# LR1302_LoRaWAN_Gateway_Module_V1_0_915SP.net
KiCad netlist of a schematic drawn in EAGLE
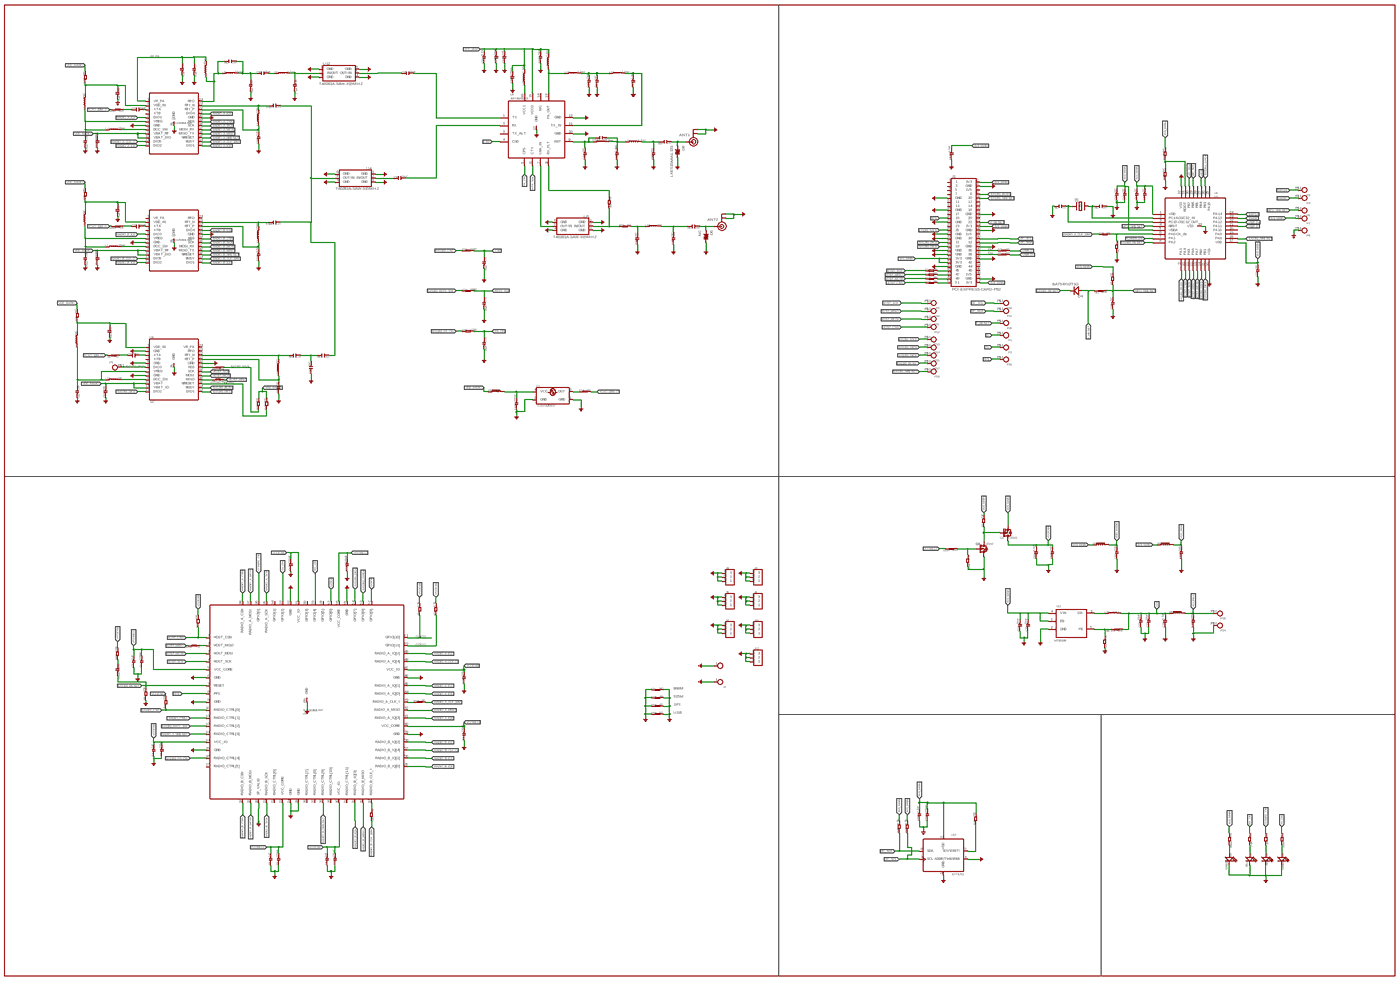
[diagram p0: schematic, sheet 1, overview]
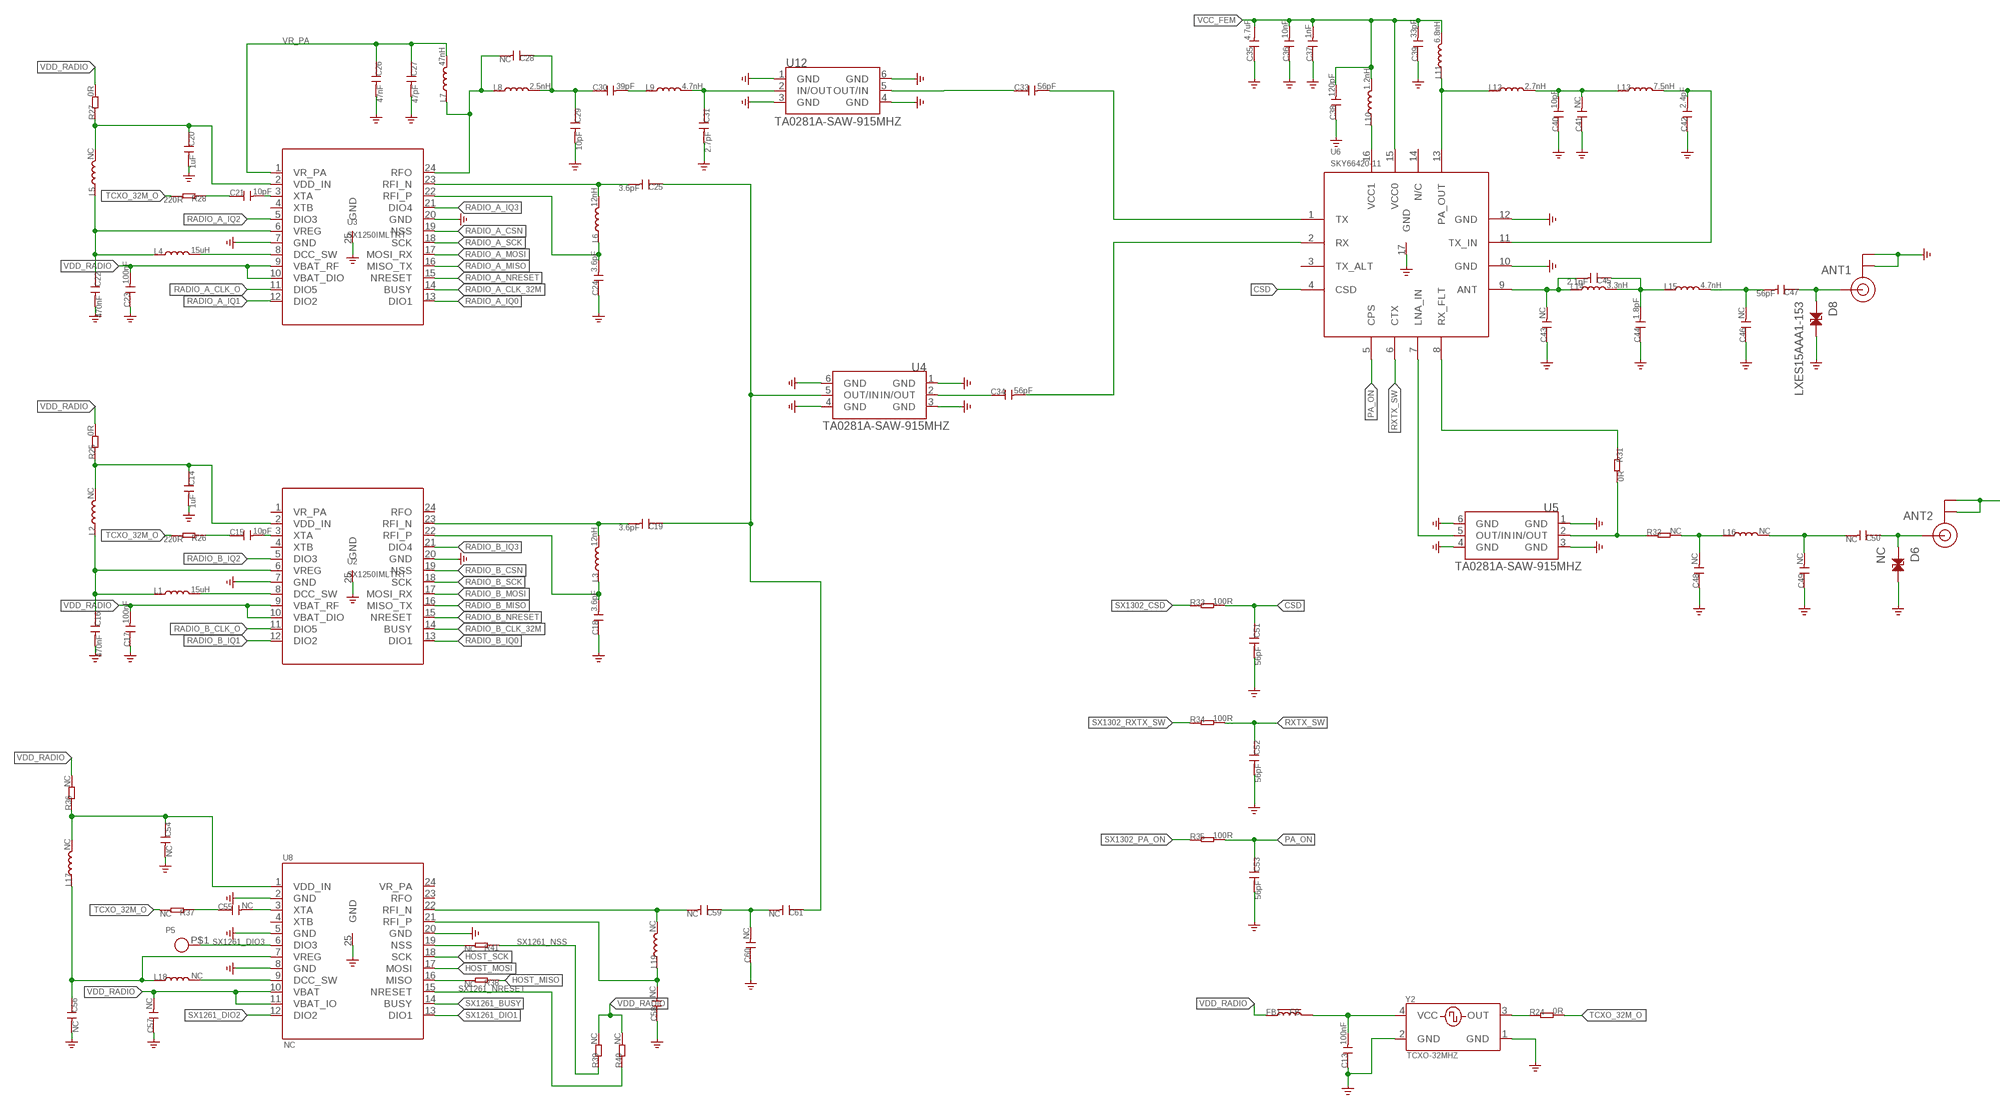
[diagram p1: schematic, sheet 1, part 1 of 4]
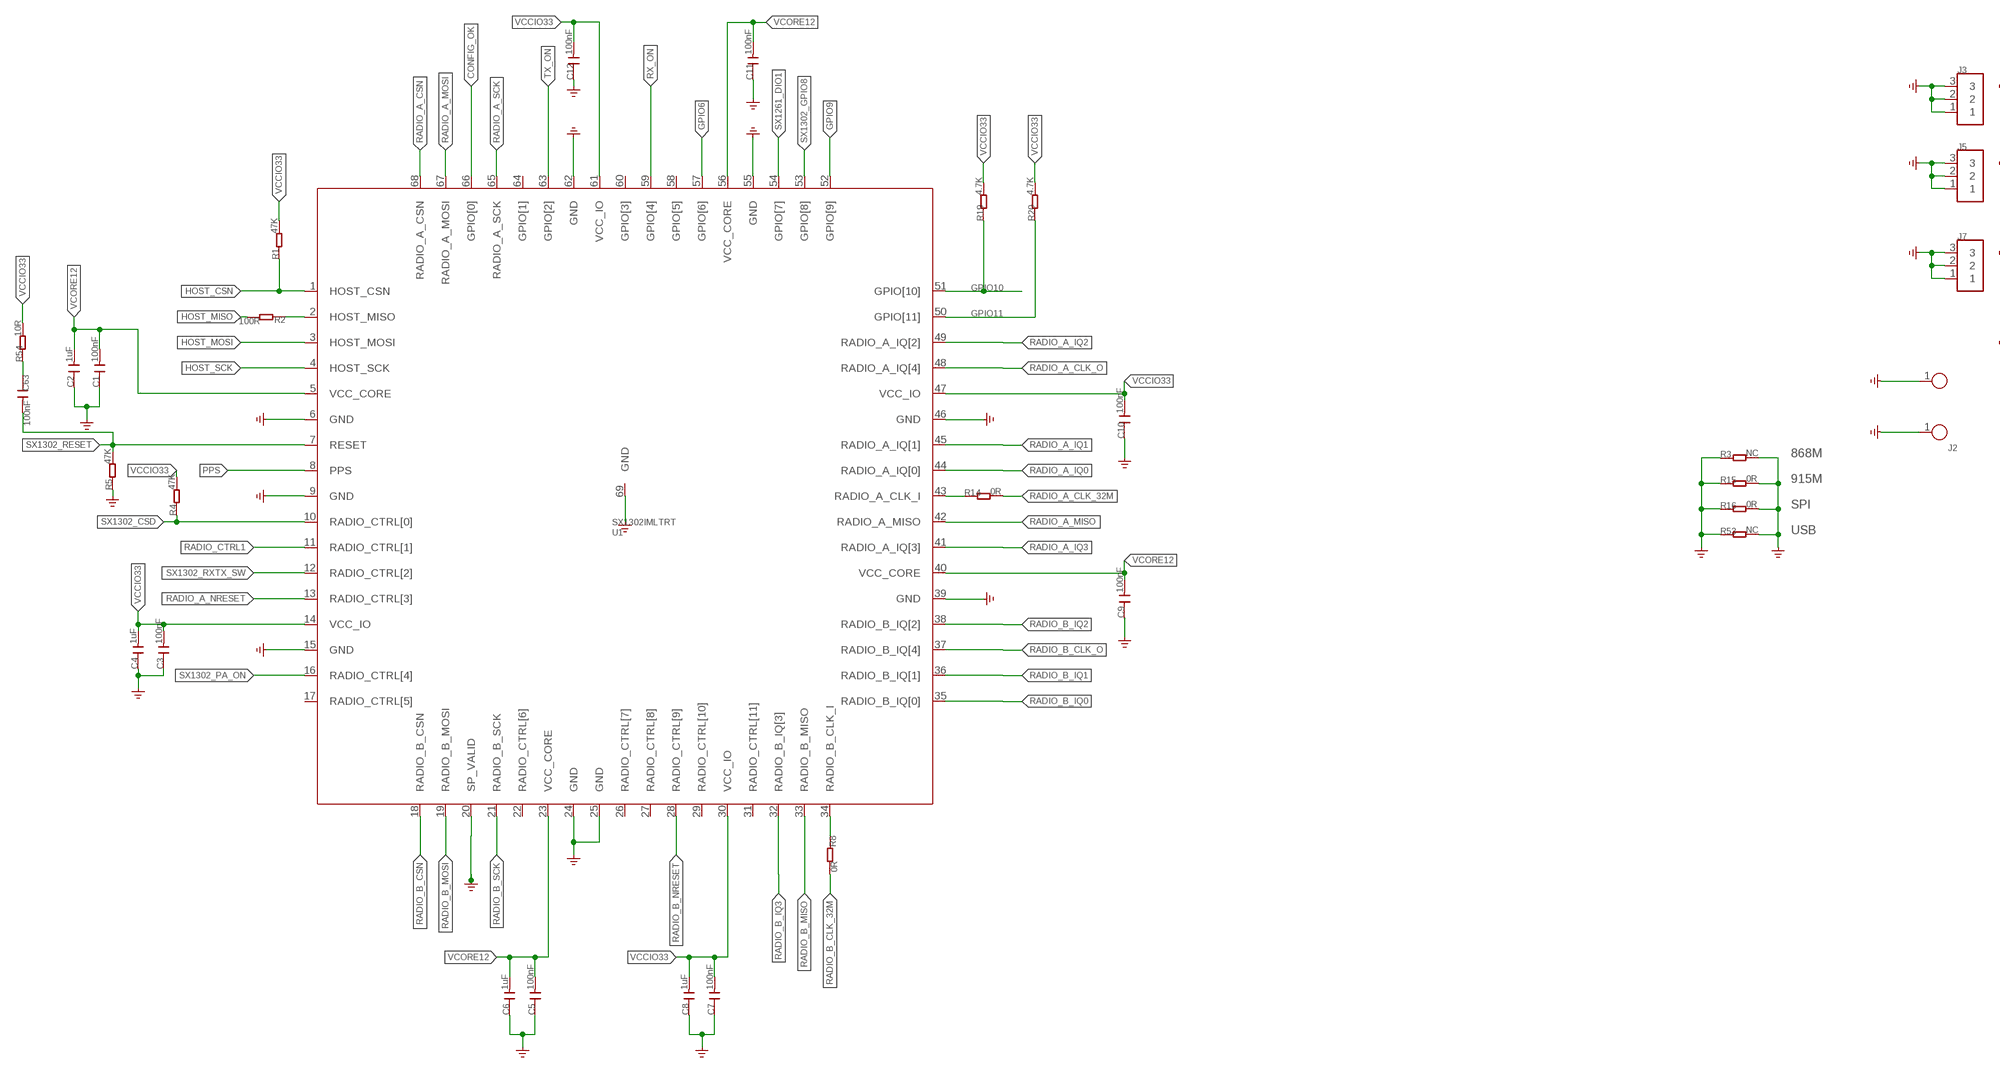
[diagram p2: schematic, sheet 1, part 2 of 4]
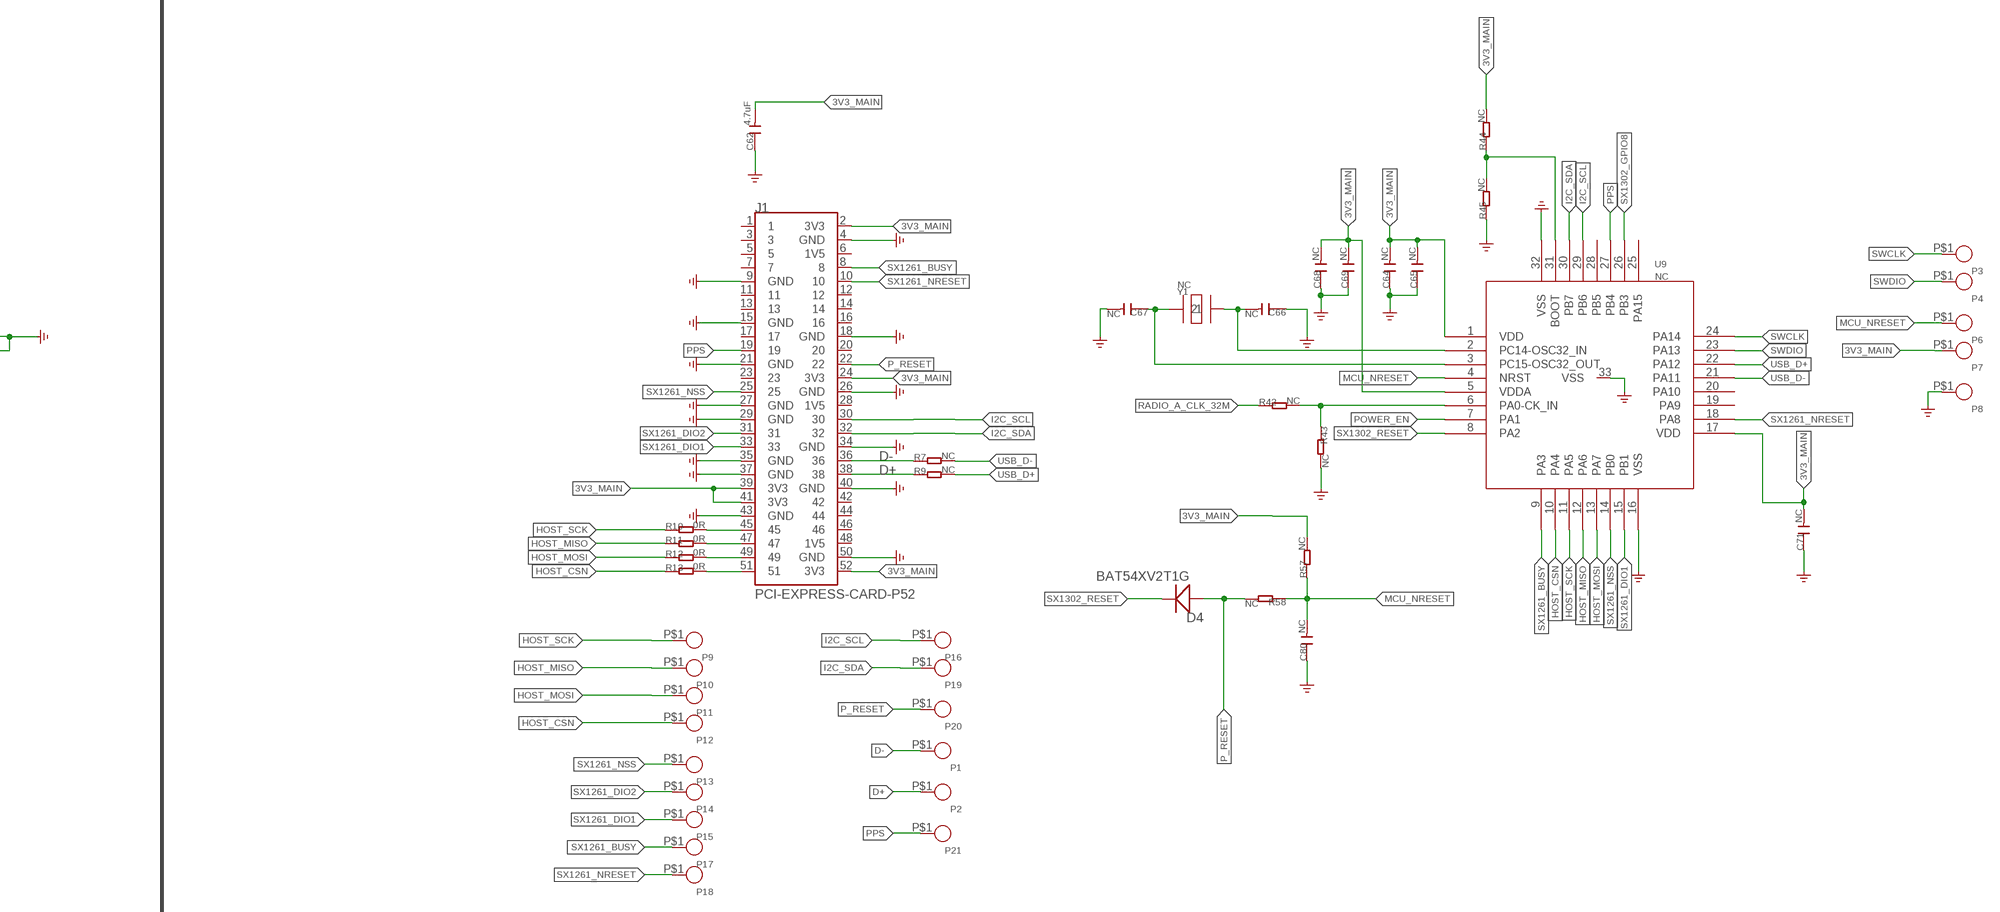
[diagram p3: schematic, sheet 1, part 3 of 4]
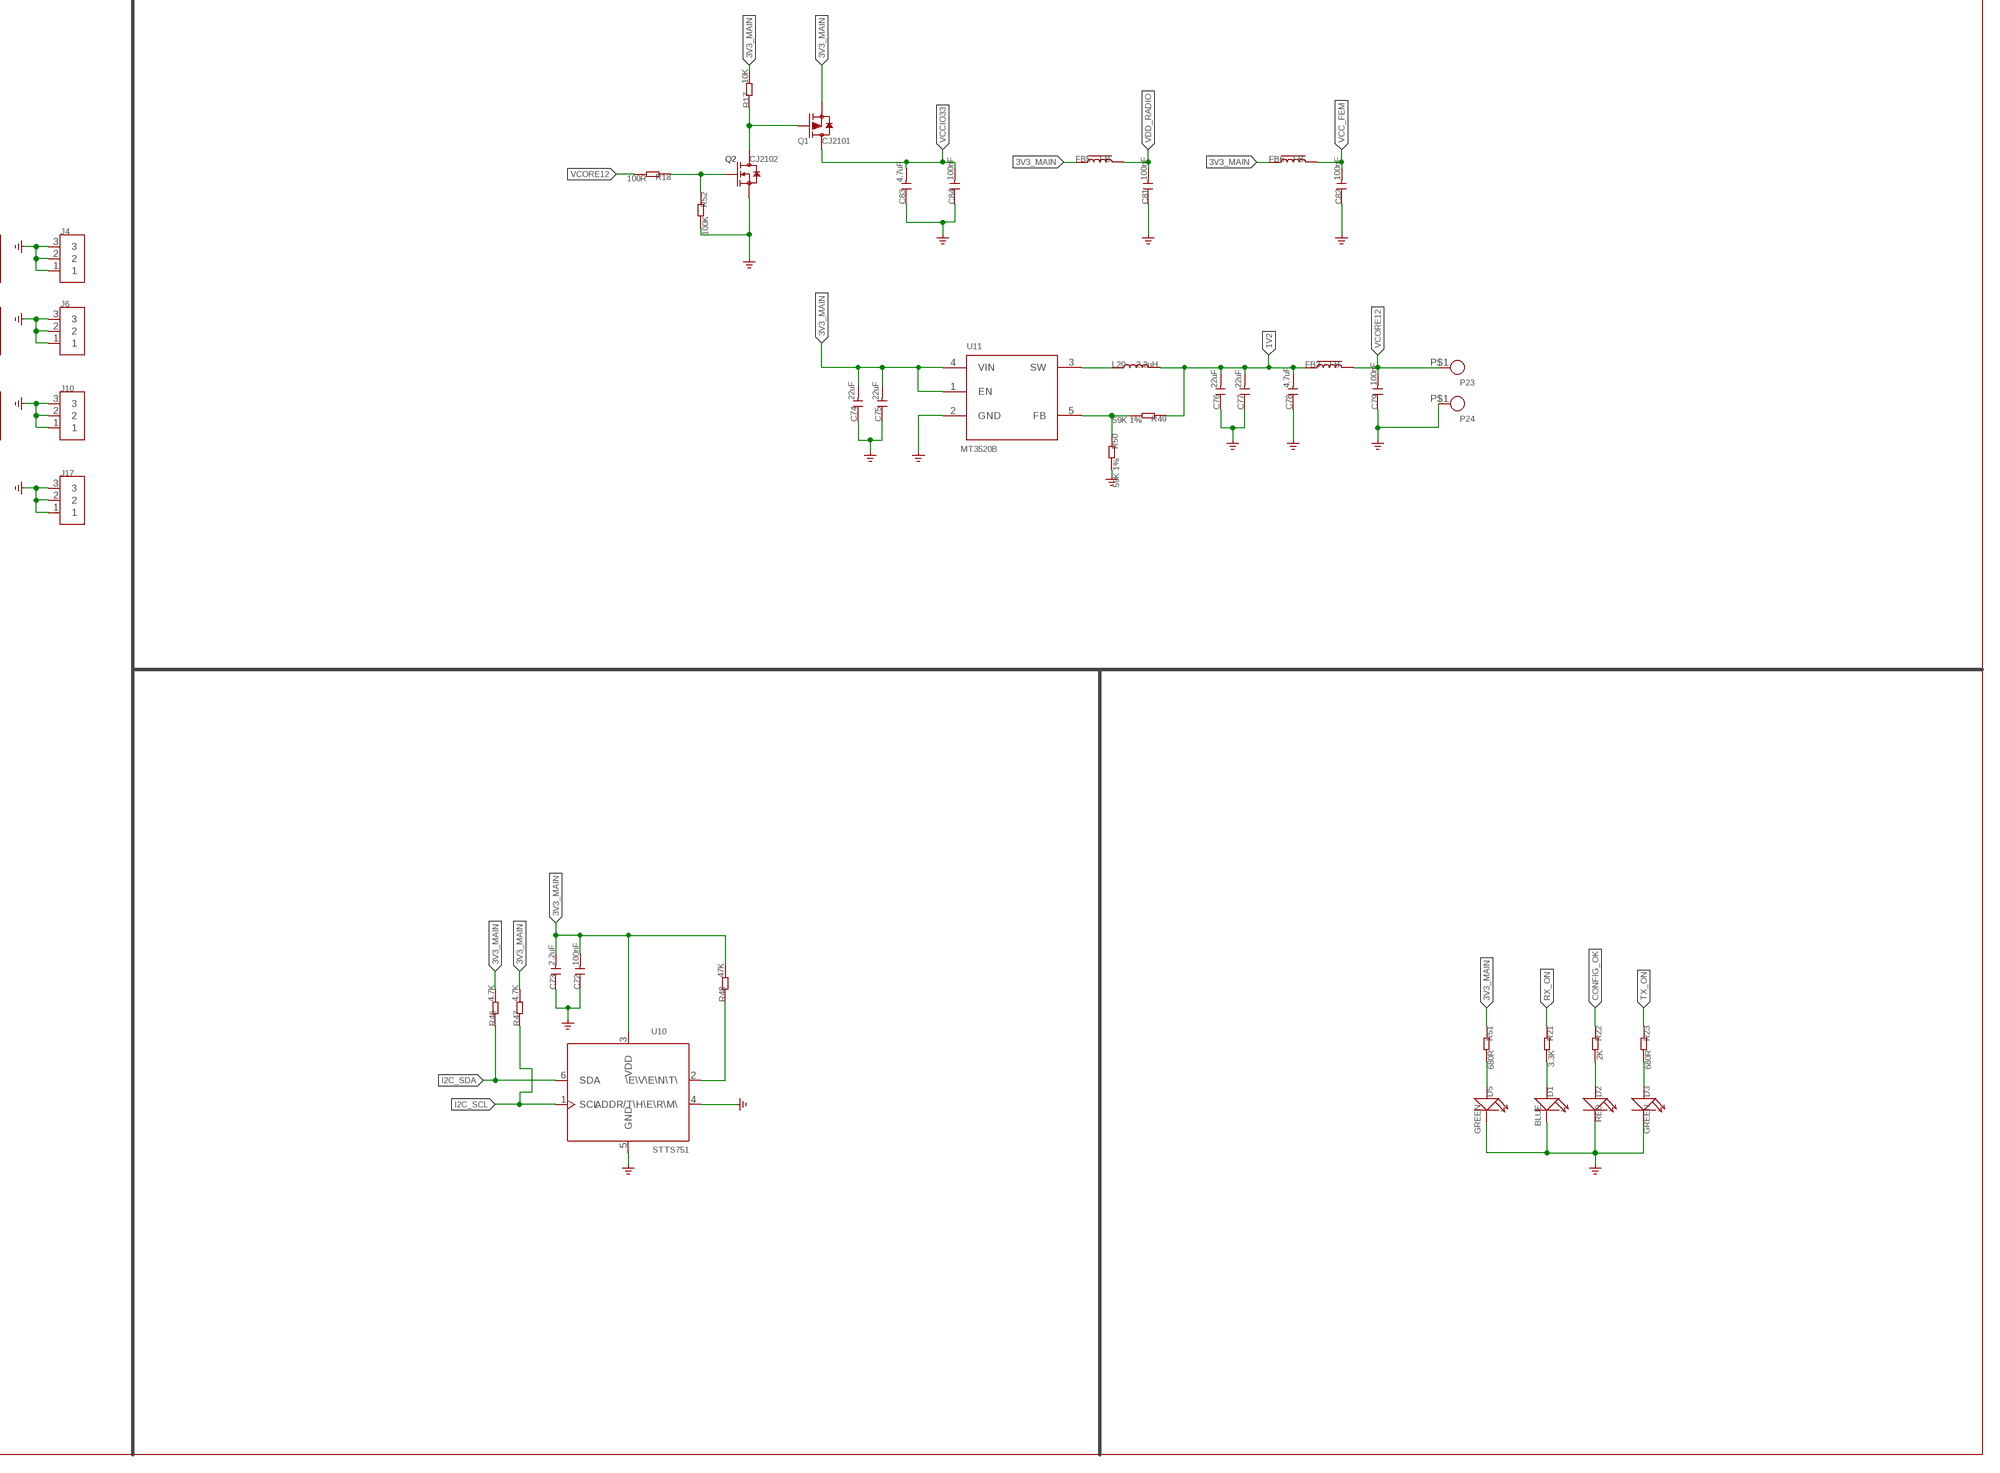
[diagram p4: schematic, sheet 1, part 4 of 4]

(export (version "E")
  (design (tool "Eeschema 10.0.6"))
  (components
    (comp (ref "ANT1")
      (value "U.FL_SMTU.FL-R-SMD")
      (footprint "eagle-import:U.FL-R-SMD")
      (libsource (lib "eagle-import") (part "U.FL_SMTU.FL-R-SMD"))
    )
    (comp (ref "ANT2")
      (value "NC")
      (footprint "eagle-import:U.FL-R-SMD")
      (libsource (lib "eagle-import") (part "U.FL_SMTU.FL-R-SMD"))
    )
    (comp (ref "C1")
      (value "100nF")
      (footprint "eagle-import:C0402")
      (libsource (lib "eagle-import") (part "CAPC0402-1"))
    )
    (comp (ref "C2")
      (value "1uF")
      (footprint "eagle-import:C0402")
      (libsource (lib "eagle-import") (part "CAPC0402-1"))
    )
    (comp (ref "C3")
      (value "100nF")
      (footprint "eagle-import:C0402")
      (libsource (lib "eagle-import") (part "CAPC0402-1"))
    )
    (comp (ref "C4")
      (value "1uF")
      (footprint "eagle-import:C0402")
      (libsource (lib "eagle-import") (part "CAPC0402-1"))
    )
    (comp (ref "C5")
      (value "100nF")
      (footprint "eagle-import:C0402")
      (libsource (lib "eagle-import") (part "CAPC0402-1"))
    )
    (comp (ref "C6")
      (value "1uF")
      (footprint "eagle-import:C0402")
      (libsource (lib "eagle-import") (part "CAPC0402-1"))
    )
    (comp (ref "C7")
      (value "100nF")
      (footprint "eagle-import:C0402")
      (libsource (lib "eagle-import") (part "CAPC0402-1"))
    )
    (comp (ref "C8")
      (value "1uF")
      (footprint "eagle-import:C0402")
      (libsource (lib "eagle-import") (part "CAPC0402-1"))
    )
    (comp (ref "C9")
      (value "100nF")
      (footprint "eagle-import:C0402")
      (libsource (lib "eagle-import") (part "CAPC0402-1"))
    )
    (comp (ref "C10")
      (value "100nF")
      (footprint "eagle-import:C0402")
      (libsource (lib "eagle-import") (part "CAPC0402-1"))
    )
    (comp (ref "C11")
      (value "100nF")
      (footprint "eagle-import:C0402")
      (libsource (lib "eagle-import") (part "CAPC0402-1"))
    )
    (comp (ref "C12")
      (value "100nF")
      (footprint "eagle-import:C0402")
      (libsource (lib "eagle-import") (part "CAPC0402-1"))
    )
    (comp (ref "C13")
      (value "100nF")
      (footprint "eagle-import:C0402")
      (libsource (lib "eagle-import") (part "CAPC0402-1"))
    )
    (comp (ref "C14")
      (value "1uF")
      (footprint "eagle-import:C0402")
      (libsource (lib "eagle-import") (part "CAPC0402-1"))
    )
    (comp (ref "C15")
      (value "10pF")
      (footprint "eagle-import:C0402")
      (libsource (lib "eagle-import") (part "CAPC0402-1"))
    )
    (comp (ref "C16")
      (value "470nF")
      (footprint "eagle-import:C0402")
      (libsource (lib "eagle-import") (part "CAPC0402-1"))
    )
    (comp (ref "C17")
      (value "100nF")
      (footprint "eagle-import:C0402")
      (libsource (lib "eagle-import") (part "CAPC0402-1"))
    )
    (comp (ref "C18")
      (value "3.6pF")
      (footprint "eagle-import:C0402")
      (libsource (lib "eagle-import") (part "CAPC0402-1"))
    )
    (comp (ref "C19")
      (value "3.6pF")
      (footprint "eagle-import:C0402")
      (libsource (lib "eagle-import") (part "CAPC0402-1"))
    )
    (comp (ref "C20")
      (value "1uF")
      (footprint "eagle-import:C0402")
      (libsource (lib "eagle-import") (part "CAPC0402-1"))
    )
    (comp (ref "C21")
      (value "10pF")
      (footprint "eagle-import:C0402")
      (libsource (lib "eagle-import") (part "CAPC0402-1"))
    )
    (comp (ref "C22")
      (value "470nF")
      (footprint "eagle-import:C0402")
      (libsource (lib "eagle-import") (part "CAPC0402-1"))
    )
    (comp (ref "C23")
      (value "100nF")
      (footprint "eagle-import:C0402")
      (libsource (lib "eagle-import") (part "CAPC0402-1"))
    )
    (comp (ref "C24")
      (value "3.6pF")
      (footprint "eagle-import:C0402")
      (libsource (lib "eagle-import") (part "CAPC0402-1"))
    )
    (comp (ref "C25")
      (value "3.6pF")
      (footprint "eagle-import:C0402")
      (libsource (lib "eagle-import") (part "CAPC0402-1"))
    )
    (comp (ref "C26")
      (value "47nF")
      (footprint "eagle-import:C0402")
      (libsource (lib "eagle-import") (part "CAPC0402-1"))
    )
    (comp (ref "C27")
      (value "47pF")
      (footprint "eagle-import:C0402")
      (libsource (lib "eagle-import") (part "CAPC0402-1"))
    )
    (comp (ref "C28")
      (value "NC")
      (footprint "eagle-import:C0402")
      (libsource (lib "eagle-import") (part "CAPC0402-1"))
    )
    (comp (ref "C29")
      (value "10pF")
      (footprint "eagle-import:C0402")
      (libsource (lib "eagle-import") (part "CAPC0402-1"))
    )
    (comp (ref "C30")
      (value "39pF")
      (footprint "eagle-import:C0402")
      (libsource (lib "eagle-import") (part "CAPC0402-1"))
    )
    (comp (ref "C31")
      (value "2.7pF")
      (footprint "eagle-import:C0402")
      (libsource (lib "eagle-import") (part "CAPC0402-1"))
    )
    (comp (ref "C33")
      (value "56pF")
      (footprint "eagle-import:C0402")
      (libsource (lib "eagle-import") (part "CAPC0402-1"))
    )
    (comp (ref "C34")
      (value "56pF")
      (footprint "eagle-import:C0402")
      (libsource (lib "eagle-import") (part "CAPC0402-1"))
    )
    (comp (ref "C35")
      (value "4.7uF")
      (footprint "eagle-import:C0603")
      (libsource (lib "eagle-import") (part "CAP"))
    )
    (comp (ref "C36")
      (value "10nF")
      (footprint "eagle-import:C0402")
      (libsource (lib "eagle-import") (part "CAPC0402-1"))
    )
    (comp (ref "C37")
      (value "1nF")
      (footprint "eagle-import:C0402")
      (libsource (lib "eagle-import") (part "CAPC0402-1"))
    )
    (comp (ref "C38")
      (value "120pF")
      (footprint "eagle-import:C0402")
      (libsource (lib "eagle-import") (part "CAPC0402-1"))
    )
    (comp (ref "C39")
      (value "33pF")
      (footprint "eagle-import:C0402")
      (libsource (lib "eagle-import") (part "CAPC0402-1"))
    )
    (comp (ref "C40")
      (value "10pF")
      (footprint "eagle-import:C0402")
      (libsource (lib "eagle-import") (part "CAPC0402-1"))
    )
    (comp (ref "C41")
      (value "NC")
      (footprint "eagle-import:C0402")
      (libsource (lib "eagle-import") (part "CAPC0402-1"))
    )
    (comp (ref "C42")
      (value "2.4pF")
      (footprint "eagle-import:C0402")
      (libsource (lib "eagle-import") (part "CAPC0402-1"))
    )
    (comp (ref "C43")
      (value "NC")
      (footprint "eagle-import:C0402")
      (libsource (lib "eagle-import") (part "CAPC0402-1"))
    )
    (comp (ref "C44")
      (value "1.8pF")
      (footprint "eagle-import:C0402")
      (libsource (lib "eagle-import") (part "CAPC0402-1"))
    )
    (comp (ref "C45")
      (value "2.1pF")
      (footprint "eagle-import:C0402")
      (libsource (lib "eagle-import") (part "CAPC0402-1"))
    )
    (comp (ref "C46")
      (value "NC")
      (footprint "eagle-import:C0402")
      (libsource (lib "eagle-import") (part "CAPC0402-1"))
    )
    (comp (ref "C47")
      (value "56pF")
      (footprint "eagle-import:C0402")
      (libsource (lib "eagle-import") (part "CAPC0402-1"))
    )
    (comp (ref "C48")
      (value "NC")
      (footprint "eagle-import:C0402")
      (libsource (lib "eagle-import") (part "CAPC0402-1"))
    )
    (comp (ref "C49")
      (value "NC")
      (footprint "eagle-import:C0402")
      (libsource (lib "eagle-import") (part "CAPC0402-1"))
    )
    (comp (ref "C50")
      (value "NC")
      (footprint "eagle-import:C0402")
      (libsource (lib "eagle-import") (part "CAPC0402-1"))
    )
    (comp (ref "C51")
      (value "56pF")
      (footprint "eagle-import:C0402")
      (libsource (lib "eagle-import") (part "CAPC0402-1"))
    )
    (comp (ref "C52")
      (value "56pF")
      (footprint "eagle-import:C0402")
      (libsource (lib "eagle-import") (part "CAPC0402-1"))
    )
    (comp (ref "C53")
      (value "56pF")
      (footprint "eagle-import:C0402")
      (libsource (lib "eagle-import") (part "CAPC0402-1"))
    )
    (comp (ref "C54")
      (value "NC")
      (footprint "eagle-import:C0402")
      (libsource (lib "eagle-import") (part "CAPC0402-1"))
    )
    (comp (ref "C55")
      (value "NC")
      (footprint "eagle-import:C0402")
      (libsource (lib "eagle-import") (part "CAPC0402-1"))
    )
    (comp (ref "C56")
      (value "NC")
      (footprint "eagle-import:C0402")
      (libsource (lib "eagle-import") (part "CAPC0402-1"))
    )
    (comp (ref "C57")
      (value "NC")
      (footprint "eagle-import:C0402")
      (libsource (lib "eagle-import") (part "CAPC0402-1"))
    )
    (comp (ref "C58")
      (value "NC")
      (footprint "eagle-import:C0402")
      (libsource (lib "eagle-import") (part "CAPC0402-1"))
    )
    (comp (ref "C59")
      (value "NC")
      (footprint "eagle-import:C0402")
      (libsource (lib "eagle-import") (part "CAPC0402-1"))
    )
    (comp (ref "C60")
      (value "NC")
      (footprint "eagle-import:C0402")
      (libsource (lib "eagle-import") (part "CAPC0402-1"))
    )
    (comp (ref "C61")
      (value "NC")
      (footprint "eagle-import:C0402")
      (libsource (lib "eagle-import") (part "CAPC0402-1"))
    )
    (comp (ref "C62")
      (value "4.7uF")
      (footprint "eagle-import:C0603")
      (libsource (lib "eagle-import") (part "CAP"))
    )
    (comp (ref "C63")
      (value "100nF")
      (footprint "eagle-import:C0402")
      (libsource (lib "eagle-import") (part "CAPC0402-1"))
    )
    (comp (ref "C64")
      (value "NC")
      (footprint "eagle-import:C0402")
      (libsource (lib "eagle-import") (part "CAPC0402-1"))
    )
    (comp (ref "C65")
      (value "NC")
      (footprint "eagle-import:C0402")
      (libsource (lib "eagle-import") (part "CAPC0402-1"))
    )
    (comp (ref "C66")
      (value "NC")
      (footprint "eagle-import:C0402")
      (libsource (lib "eagle-import") (part "CAPC0402-1"))
    )
    (comp (ref "C67")
      (value "NC")
      (footprint "eagle-import:C0402")
      (libsource (lib "eagle-import") (part "CAPC0402-1"))
    )
    (comp (ref "C68")
      (value "NC")
      (footprint "eagle-import:C0402")
      (libsource (lib "eagle-import") (part "CAPC0402-1"))
    )
    (comp (ref "C69")
      (value "NC")
      (footprint "eagle-import:C0402")
      (libsource (lib "eagle-import") (part "CAPC0402-1"))
    )
    (comp (ref "C71")
      (value "NC")
      (footprint "eagle-import:C0402")
      (libsource (lib "eagle-import") (part "CAPC0402-1"))
    )
    (comp (ref "C72")
      (value "100nF")
      (footprint "eagle-import:C0402")
      (libsource (lib "eagle-import") (part "CAPC0402-1"))
    )
    (comp (ref "C73")
      (value "2.2uF")
      (footprint "eagle-import:C0402")
      (libsource (lib "eagle-import") (part "CAPC0402-1"))
    )
    (comp (ref "C74")
      (value "22uF")
      (footprint "eagle-import:C0603")
      (libsource (lib "eagle-import") (part "CAP"))
    )
    (comp (ref "C75")
      (value "22uF")
      (footprint "eagle-import:C0603")
      (libsource (lib "eagle-import") (part "CAP"))
    )
    (comp (ref "C76")
      (value "22uF")
      (footprint "eagle-import:C0603")
      (libsource (lib "eagle-import") (part "CAP"))
    )
    (comp (ref "C77")
      (value "22uF")
      (footprint "eagle-import:C0603")
      (libsource (lib "eagle-import") (part "CAP"))
    )
    (comp (ref "C78")
      (value "4.7uF")
      (footprint "eagle-import:C0603")
      (libsource (lib "eagle-import") (part "CAP"))
    )
    (comp (ref "C79")
      (value "100nF")
      (footprint "eagle-import:C0402")
      (libsource (lib "eagle-import") (part "CAPC0402-1"))
    )
    (comp (ref "C80")
      (value "NC")
      (footprint "eagle-import:C0402")
      (libsource (lib "eagle-import") (part "CAPC0402-1"))
    )
    (comp (ref "C81")
      (value "100nF")
      (footprint "eagle-import:C0402")
      (libsource (lib "eagle-import") (part "CAPC0402-1"))
    )
    (comp (ref "C82")
      (value "100nF")
      (footprint "eagle-import:C0402")
      (libsource (lib "eagle-import") (part "CAPC0402-1"))
    )
    (comp (ref "C83")
      (value "4.7uF")
      (footprint "eagle-import:C0603")
      (libsource (lib "eagle-import") (part "CAP"))
    )
    (comp (ref "C84")
      (value "100nF")
      (footprint "eagle-import:C0402")
      (libsource (lib "eagle-import") (part "CAPC0402-1"))
    )
    (comp (ref "D1")
      (value "BLUE")
      (footprint "eagle-import:LED-0402")
      (libsource (lib "eagle-import") (part "LED-SMT"))
    )
    (comp (ref "D2")
      (value "RED")
      (footprint "eagle-import:LED-0402")
      (libsource (lib "eagle-import") (part "LED-SMT"))
    )
    (comp (ref "D3")
      (value "GREEN")
      (footprint "eagle-import:LED-0402")
      (libsource (lib "eagle-import") (part "LED-SMT"))
    )
    (comp (ref "D4")
      (value "BAT54XV2T1G")
      (footprint "eagle-import:D_SOD523")
      (libsource (lib "eagle-import") (part "DIODE0603"))
    )
    (comp (ref "D5")
      (value "GREEN")
      (footprint "eagle-import:LED-0402")
      (libsource (lib "eagle-import") (part "LED-SMT"))
    )
    (comp (ref "D6")
      (value "NC")
      (footprint "eagle-import:D0402")
      (libsource (lib "eagle-import") (part "PESD0402"))
    )
    (comp (ref "D8")
      (value "LXES15AAA1-153")
      (footprint "eagle-import:D0402")
      (libsource (lib "eagle-import") (part "PESD0402"))
    )
    (comp (ref "FB1")
      (value "FB")
      (footprint "eagle-import:L0402")
      (libsource (lib "eagle-import") (part "FB"))
    )
    (comp (ref "FB3")
      (value "FB")
      (footprint "eagle-import:L0402")
      (libsource (lib "eagle-import") (part "FB"))
    )
    (comp (ref "FB5")
      (value "FB")
      (footprint "eagle-import:L0402")
      (libsource (lib "eagle-import") (part "FB"))
    )
    (comp (ref "FB6")
      (value "FB")
      (footprint "eagle-import:L0402")
      (libsource (lib "eagle-import") (part "FB"))
    )
    (comp (ref "J1")
      (value "PCI-EXPRESS-CARD-P52")
      (footprint "eagle-import:PCIE-MINI-S52")
      (libsource (lib "eagle-import") (part "PCI-EXPRESS-CARD-P52"))
    )
    (comp (ref "J2")
      (value "PAD-THO-2.65MM")
      (footprint "eagle-import:PAD-THO-2.6_5MM")
      (libsource (lib "eagle-import") (part "PAD-THO-2.65MM"))
    )
    (comp (ref "J3")
      (value "PBJ-ICSRC6508-SMD")
      (footprint "eagle-import:PBJ-ICSRC6508-SMD")
      (libsource (lib "eagle-import") (part "PBJ-ICSRC6508-SMD"))
    )
    (comp (ref "J4")
      (value "PBJ-ICSRC6508-SMD")
      (footprint "eagle-import:PBJ-ICSRC6508-SMD")
      (libsource (lib "eagle-import") (part "PBJ-ICSRC6508-SMD"))
    )
    (comp (ref "J5")
      (value "PBJ-ICSRC6508-SMD")
      (footprint "eagle-import:PBJ-ICSRC6508-SMD")
      (libsource (lib "eagle-import") (part "PBJ-ICSRC6508-SMD"))
    )
    (comp (ref "J6")
      (value "PBJ-ICSRC6508-SMD")
      (footprint "eagle-import:PBJ-ICSRC6508-SMD")
      (libsource (lib "eagle-import") (part "PBJ-ICSRC6508-SMD"))
    )
    (comp (ref "J7")
      (value "PBJ-ICSRC6508-SMD")
      (footprint "eagle-import:PBJ-ICSRC6508-SMD")
      (libsource (lib "eagle-import") (part "PBJ-ICSRC6508-SMD"))
    )
    (comp (ref "J10")
      (value "PBJ-ICSRC6508-SMD")
      (footprint "eagle-import:PBJ-ICSRC6508-SMD")
      (libsource (lib "eagle-import") (part "PBJ-ICSRC6508-SMD"))
    )
    (comp (ref "J11")
      (value "PAD-THO-2.65MM")
      (footprint "eagle-import:PAD-THO-2.6_5MM")
      (libsource (lib "eagle-import") (part "PAD-THO-2.65MM"))
    )
    (comp (ref "J17")
      (value "PBJ-ICSRC6508-SMD")
      (footprint "eagle-import:PBJ-ICSRC6508-SMD")
      (libsource (lib "eagle-import") (part "PBJ-ICSRC6508-SMD"))
    )
    (comp (ref "L1")
      (value "15uH")
      (footprint "eagle-import:L0805")
      (libsource (lib "eagle-import") (part "L0805"))
    )
    (comp (ref "L2")
      (value "NC")
      (footprint "eagle-import:L0402")
      (libsource (lib "eagle-import") (part "L0402"))
    )
    (comp (ref "L3")
      (value "12nH")
      (footprint "eagle-import:L0402")
      (libsource (lib "eagle-import") (part "L0402"))
    )
    (comp (ref "L4")
      (value "15uH")
      (footprint "eagle-import:L0805")
      (libsource (lib "eagle-import") (part "L0805"))
    )
    (comp (ref "L5")
      (value "NC")
      (footprint "eagle-import:L0402")
      (libsource (lib "eagle-import") (part "L0402"))
    )
    (comp (ref "L6")
      (value "12nH")
      (footprint "eagle-import:L0402")
      (libsource (lib "eagle-import") (part "L0402"))
    )
    (comp (ref "L7")
      (value "47nH")
      (footprint "eagle-import:L0402")
      (libsource (lib "eagle-import") (part "L0402"))
    )
    (comp (ref "L8")
      (value "2.5nH")
      (footprint "eagle-import:L0402")
      (libsource (lib "eagle-import") (part "L0402"))
    )
    (comp (ref "L9")
      (value "4.7nH")
      (footprint "eagle-import:L0402")
      (libsource (lib "eagle-import") (part "L0402"))
    )
    (comp (ref "L10")
      (value "1.2nH")
      (footprint "eagle-import:L0402")
      (libsource (lib "eagle-import") (part "L0402"))
    )
    (comp (ref "L11")
      (value "6.8nH")
      (footprint "eagle-import:L0402")
      (libsource (lib "eagle-import") (part "L0402"))
    )
    (comp (ref "L12")
      (value "2.7nH")
      (footprint "eagle-import:L0402")
      (libsource (lib "eagle-import") (part "L0402"))
    )
    (comp (ref "L13")
      (value "7.5nH")
      (footprint "eagle-import:L0402")
      (libsource (lib "eagle-import") (part "L0402"))
    )
    (comp (ref "L14")
      (value "3.3nH")
      (footprint "eagle-import:L0402")
      (libsource (lib "eagle-import") (part "L0402"))
    )
    (comp (ref "L15")
      (value "4.7nH")
      (footprint "eagle-import:L0402")
      (libsource (lib "eagle-import") (part "L0402"))
    )
    (comp (ref "L16")
      (value "NC")
      (footprint "eagle-import:L0402")
      (libsource (lib "eagle-import") (part "L0402"))
    )
    (comp (ref "L17")
      (value "NC")
      (footprint "eagle-import:L0402")
      (libsource (lib "eagle-import") (part "L0402"))
    )
    (comp (ref "L18")
      (value "NC")
      (footprint "eagle-import:L0805")
      (libsource (lib "eagle-import") (part "L0805"))
    )
    (comp (ref "L19")
      (value "NC")
      (footprint "eagle-import:L0402")
      (libsource (lib "eagle-import") (part "L0402"))
    )
    (comp (ref "L20")
      (value "2.2uH")
      (footprint "eagle-import:L3015_SMD")
      (libsource (lib "eagle-import") (part "L"))
    )
    (comp (ref "P1")
      (value "TEST_PADPAD-1.0MM")
      (footprint "eagle-import:TEST_PAD-1.0MM")
      (libsource (lib "eagle-import") (part "TEST_PADPAD-1.0MM"))
    )
    (comp (ref "P2")
      (value "TEST_PADPAD-1.0MM")
      (footprint "eagle-import:TEST_PAD-1.0MM")
      (libsource (lib "eagle-import") (part "TEST_PADPAD-1.0MM"))
    )
    (comp (ref "P3")
      (value "TEST_PADPAD-1.0MM")
      (footprint "eagle-import:TEST_PAD-1.0MM")
      (libsource (lib "eagle-import") (part "TEST_PADPAD-1.0MM"))
    )
    (comp (ref "P4")
      (value "TEST_PADPAD-1.0MM")
      (footprint "eagle-import:TEST_PAD-1.0MM")
      (libsource (lib "eagle-import") (part "TEST_PADPAD-1.0MM"))
    )
    (comp (ref "P5")
      (value "TEST_PADPAD-1.0MM")
      (footprint "eagle-import:TEST_PAD-1.0MM")
      (libsource (lib "eagle-import") (part "TEST_PADPAD-1.0MM"))
    )
    (comp (ref "P6")
      (value "TEST_PADPAD-1.0MM")
      (footprint "eagle-import:TEST_PAD-1.0MM")
      (libsource (lib "eagle-import") (part "TEST_PADPAD-1.0MM"))
    )
    (comp (ref "P7")
      (value "TEST_PADPAD-1.0MM")
      (footprint "eagle-import:TEST_PAD-1.0MM")
      (libsource (lib "eagle-import") (part "TEST_PADPAD-1.0MM"))
    )
    (comp (ref "P8")
      (value "TEST_PADPAD-1.0MM")
      (footprint "eagle-import:TEST_PAD-1.0MM")
      (libsource (lib "eagle-import") (part "TEST_PADPAD-1.0MM"))
    )
    (comp (ref "P9")
      (value "TEST_PADPAD-1.0MM")
      (footprint "eagle-import:TEST_PAD-1.0MM")
      (libsource (lib "eagle-import") (part "TEST_PADPAD-1.0MM"))
    )
    (comp (ref "P10")
      (value "TEST_PADPAD-1.0MM")
      (footprint "eagle-import:TEST_PAD-1.0MM")
      (libsource (lib "eagle-import") (part "TEST_PADPAD-1.0MM"))
    )
    (comp (ref "P11")
      (value "TEST_PADPAD-1.0MM")
      (footprint "eagle-import:TEST_PAD-1.0MM")
      (libsource (lib "eagle-import") (part "TEST_PADPAD-1.0MM"))
    )
    (comp (ref "P12")
      (value "TEST_PADPAD-1.0MM")
      (footprint "eagle-import:TEST_PAD-1.0MM")
      (libsource (lib "eagle-import") (part "TEST_PADPAD-1.0MM"))
    )
    (comp (ref "P13")
      (value "TEST_PADPAD-1.0MM")
      (footprint "eagle-import:TEST_PAD-1.0MM")
      (libsource (lib "eagle-import") (part "TEST_PADPAD-1.0MM"))
    )
    (comp (ref "P14")
      (value "TEST_PADPAD-1.0MM")
      (footprint "eagle-import:TEST_PAD-1.0MM")
      (libsource (lib "eagle-import") (part "TEST_PADPAD-1.0MM"))
    )
    (comp (ref "P15")
      (value "TEST_PADPAD-1.0MM")
      (footprint "eagle-import:TEST_PAD-1.0MM")
      (libsource (lib "eagle-import") (part "TEST_PADPAD-1.0MM"))
    )
    (comp (ref "P16")
      (value "TEST_PADPAD-1.0MM")
      (footprint "eagle-import:TEST_PAD-1.0MM")
      (libsource (lib "eagle-import") (part "TEST_PADPAD-1.0MM"))
    )
    (comp (ref "P17")
      (value "TEST_PADPAD-1.0MM")
      (footprint "eagle-import:TEST_PAD-1.0MM")
      (libsource (lib "eagle-import") (part "TEST_PADPAD-1.0MM"))
    )
    (comp (ref "P18")
      (value "TEST_PADPAD-1.0MM")
      (footprint "eagle-import:TEST_PAD-1.0MM")
      (libsource (lib "eagle-import") (part "TEST_PADPAD-1.0MM"))
    )
    (comp (ref "P19")
      (value "TEST_PADPAD-1.0MM")
      (footprint "eagle-import:TEST_PAD-1.0MM")
      (libsource (lib "eagle-import") (part "TEST_PADPAD-1.0MM"))
    )
    (comp (ref "P20")
      (value "TEST_PADPAD-1.0MM")
      (footprint "eagle-import:TEST_PAD-1.0MM")
      (libsource (lib "eagle-import") (part "TEST_PADPAD-1.0MM"))
    )
    (comp (ref "P21")
      (value "TEST_PADPAD-1.0MM")
      (footprint "eagle-import:TEST_PAD-1.0MM")
      (libsource (lib "eagle-import") (part "TEST_PADPAD-1.0MM"))
    )
    (comp (ref "P23")
      (value "TEST_PADPAD-1.0MM")
      (footprint "eagle-import:TEST_PAD-1.0MM")
      (libsource (lib "eagle-import") (part "TEST_PADPAD-1.0MM"))
    )
    (comp (ref "P24")
      (value "TEST_PADPAD-1.0MM")
      (footprint "eagle-import:TEST_PAD-1.0MM")
      (libsource (lib "eagle-import") (part "TEST_PADPAD-1.0MM"))
    )
    (comp (ref "Q1")
      (value "CJ2101")
      (footprint "eagle-import:MOS_SOT323")
      (libsource (lib "eagle-import") (part "MOSFET-P"))
    )
    (comp (ref "Q2")
      (value "CJ2102")
      (footprint "eagle-import:MOS_SOT323")
      (libsource (lib "eagle-import") (part "MOSFET-NSI1304BDL"))
    )
    (comp (ref "R1")
      (value "47K")
      (footprint "eagle-import:R0402")
      (libsource (lib "eagle-import") (part "RES-0402"))
    )
    (comp (ref "R2")
      (value "100R")
      (footprint "eagle-import:R0402")
      (libsource (lib "eagle-import") (part "RES-0402"))
    )
    (comp (ref "R3")
      (value "NC")
      (footprint "eagle-import:R0402")
      (libsource (lib "eagle-import") (part "RES-0402"))
    )
    (comp (ref "R4")
      (value "47K")
      (footprint "eagle-import:R0402")
      (libsource (lib "eagle-import") (part "RES-0402"))
    )
    (comp (ref "R5")
      (value "47K")
      (footprint "eagle-import:R0402")
      (libsource (lib "eagle-import") (part "RES-0402"))
    )
    (comp (ref "R7")
      (value "NC")
      (footprint "eagle-import:R0402")
      (libsource (lib "eagle-import") (part "RES-0402"))
    )
    (comp (ref "R8")
      (value "0R")
      (footprint "eagle-import:R0402")
      (libsource (lib "eagle-import") (part "RES-0402"))
    )
    (comp (ref "R9")
      (value "NC")
      (footprint "eagle-import:R0402")
      (libsource (lib "eagle-import") (part "RES-0402"))
    )
    (comp (ref "R10")
      (value "0R")
      (footprint "eagle-import:R0402")
      (libsource (lib "eagle-import") (part "RES-0402"))
    )
    (comp (ref "R11")
      (value "0R")
      (footprint "eagle-import:R0402")
      (libsource (lib "eagle-import") (part "RES-0402"))
    )
    (comp (ref "R12")
      (value "0R")
      (footprint "eagle-import:R0402")
      (libsource (lib "eagle-import") (part "RES-0402"))
    )
    (comp (ref "R13")
      (value "0R")
      (footprint "eagle-import:R0402")
      (libsource (lib "eagle-import") (part "RES-0402"))
    )
    (comp (ref "R14")
      (value "0R")
      (footprint "eagle-import:R0402")
      (libsource (lib "eagle-import") (part "RES-0402"))
    )
    (comp (ref "R15")
      (value "0R")
      (footprint "eagle-import:R0402")
      (libsource (lib "eagle-import") (part "RES-0402"))
    )
    (comp (ref "R16")
      (value "0R")
      (footprint "eagle-import:R0402")
      (libsource (lib "eagle-import") (part "RES-0402"))
    )
    (comp (ref "R17")
      (value "10K")
      (footprint "eagle-import:R0402")
      (libsource (lib "eagle-import") (part "RES-0402"))
    )
    (comp (ref "R18")
      (value "100R")
      (footprint "eagle-import:R0402")
      (libsource (lib "eagle-import") (part "RES-0402"))
    )
    (comp (ref "R19")
      (value "4.7K")
      (footprint "eagle-import:R0402")
      (libsource (lib "eagle-import") (part "RES-0402"))
    )
    (comp (ref "R20")
      (value "4.7K")
      (footprint "eagle-import:R0402")
      (libsource (lib "eagle-import") (part "RES-0402"))
    )
    (comp (ref "R21")
      (value "3.3K")
      (footprint "eagle-import:R0402")
      (libsource (lib "eagle-import") (part "RES-0402"))
    )
    (comp (ref "R22")
      (value "2K")
      (footprint "eagle-import:R0402")
      (libsource (lib "eagle-import") (part "RES-0402"))
    )
    (comp (ref "R23")
      (value "680R")
      (footprint "eagle-import:R0402")
      (libsource (lib "eagle-import") (part "RES-0402"))
    )
    (comp (ref "R24")
      (value "0R")
      (footprint "eagle-import:R0402")
      (libsource (lib "eagle-import") (part "RES-0402"))
    )
    (comp (ref "R25")
      (value "0R")
      (footprint "eagle-import:R0402")
      (libsource (lib "eagle-import") (part "RES-0402"))
    )
    (comp (ref "R26")
      (value "220R")
      (footprint "eagle-import:R0402")
      (libsource (lib "eagle-import") (part "RES-0402"))
    )
    (comp (ref "R27")
      (value "0R")
      (footprint "eagle-import:R0402")
      (libsource (lib "eagle-import") (part "RES-0402"))
    )
    (comp (ref "R28")
      (value "220R")
      (footprint "eagle-import:R0402")
      (libsource (lib "eagle-import") (part "RES-0402"))
    )
    (comp (ref "R31")
      (value "0R")
      (footprint "eagle-import:R0402")
      (libsource (lib "eagle-import") (part "RES-0402"))
    )
    (comp (ref "R32")
      (value "NC")
      (footprint "eagle-import:R0402")
      (libsource (lib "eagle-import") (part "RES-0402"))
    )
    (comp (ref "R33")
      (value "100R")
      (footprint "eagle-import:R0402")
      (libsource (lib "eagle-import") (part "RES-0402"))
    )
    (comp (ref "R34")
      (value "100R")
      (footprint "eagle-import:R0402")
      (libsource (lib "eagle-import") (part "RES-0402"))
    )
    (comp (ref "R35")
      (value "100R")
      (footprint "eagle-import:R0402")
      (libsource (lib "eagle-import") (part "RES-0402"))
    )
    (comp (ref "R36")
      (value "NC")
      (footprint "eagle-import:R0402")
      (libsource (lib "eagle-import") (part "RES-0402"))
    )
    (comp (ref "R37")
      (value "NC")
      (footprint "eagle-import:R0402")
      (libsource (lib "eagle-import") (part "RES-0402"))
    )
    (comp (ref "R38")
      (value "NC")
      (footprint "eagle-import:R0402")
      (libsource (lib "eagle-import") (part "RES-0402"))
    )
    (comp (ref "R39")
      (value "NC")
      (footprint "eagle-import:R0402")
      (libsource (lib "eagle-import") (part "RES-0402"))
    )
    (comp (ref "R40")
      (value "NC")
      (footprint "eagle-import:R0402")
      (libsource (lib "eagle-import") (part "RES-0402"))
    )
    (comp (ref "R41")
      (value "NC")
      (footprint "eagle-import:R0402")
      (libsource (lib "eagle-import") (part "RES-0402"))
    )
    (comp (ref "R42")
      (value "NC")
      (footprint "eagle-import:R0402")
      (libsource (lib "eagle-import") (part "RES-0402"))
    )
    (comp (ref "R43")
      (value "NC")
      (footprint "eagle-import:R0402")
      (libsource (lib "eagle-import") (part "RES-0402"))
    )
    (comp (ref "R44")
      (value "NC")
      (footprint "eagle-import:R0402")
      (libsource (lib "eagle-import") (part "RES-0402"))
    )
    (comp (ref "R45")
      (value "NC")
      (footprint "eagle-import:R0402")
      (libsource (lib "eagle-import") (part "RES-0402"))
    )
    (comp (ref "R46")
      (value "4.7K")
      (footprint "eagle-import:R0402")
      (libsource (lib "eagle-import") (part "RES-0402"))
    )
    (comp (ref "R47")
      (value "4.7K")
      (footprint "eagle-import:R0402")
      (libsource (lib "eagle-import") (part "RES-0402"))
    )
    (comp (ref "R48")
      (value "47K")
      (footprint "eagle-import:R0402")
      (libsource (lib "eagle-import") (part "RES-0402"))
    )
    (comp (ref "R49")
      (value "59K 1%")
      (footprint "eagle-import:R0402")
      (libsource (lib "eagle-import") (part "RES-0402"))
    )
    (comp (ref "R50")
      (value "59K 1%")
      (footprint "eagle-import:R0402")
      (libsource (lib "eagle-import") (part "RES-0402"))
    )
    (comp (ref "R51")
      (value "680R")
      (footprint "eagle-import:R0402")
      (libsource (lib "eagle-import") (part "RES-0402"))
    )
    (comp (ref "R52")
      (value "100K")
      (footprint "eagle-import:R0402")
      (libsource (lib "eagle-import") (part "RES-0402"))
    )
    (comp (ref "R53")
      (value "NC")
      (footprint "eagle-import:R0402")
      (libsource (lib "eagle-import") (part "RES-0402"))
    )
    (comp (ref "R54")
      (value "10R")
      (footprint "eagle-import:R0402")
      (libsource (lib "eagle-import") (part "RES-0402"))
    )
    (comp (ref "R57")
      (value "NC")
      (footprint "eagle-import:R0402")
      (libsource (lib "eagle-import") (part "RES-0402"))
    )
    (comp (ref "R58")
      (value "NC")
      (footprint "eagle-import:R0402")
      (libsource (lib "eagle-import") (part "RES-0402"))
    )
    (comp (ref "U1")
      (value "SX1302IMLTRT")
      (footprint "eagle-import:QFN68-7_7MM")
      (libsource (lib "eagle-import") (part "SX1302IMLTRT"))
    )
    (comp (ref "U2")
      (value "SX1250IMLTRT")
      (footprint "eagle-import:QFN24-4_4MM")
      (libsource (lib "eagle-import") (part "SX1250IMLTRT"))
    )
    (comp (ref "U3")
      (value "SX1250IMLTRT")
      (footprint "eagle-import:QFN24-4_4MM")
      (libsource (lib "eagle-import") (part "SX1250IMLTRT"))
    )
    (comp (ref "U4")
      (value "TA0281A-SAW-915MHZ")
      (footprint "eagle-import:SAW-SMD6-3_3MM")
      (libsource (lib "eagle-import") (part "TA0801A-SAW-868MHZ"))
    )
    (comp (ref "U5")
      (value "TA0281A-SAW-915MHZ")
      (footprint "eagle-import:SAW-SMD6-3_3MM")
      (libsource (lib "eagle-import") (part "TA0801A-SAW-868MHZ"))
    )
    (comp (ref "U6")
      (value "SKY66420-11")
      (footprint "eagle-import:MCM-16-EP(3X3)")
      (libsource (lib "eagle-import") (part "SKY66420-11"))
    )
    (comp (ref "U8")
      (value "NC")
      (footprint "eagle-import:QFN24-4_4MM")
      (libsource (lib "eagle-import") (part "SX1261IMLTRT"))
    )
    (comp (ref "U9")
      (value "NC")
      (footprint "eagle-import:UFQFPN-32-5_5MM")
      (libsource (lib "eagle-import") (part "STM32L412KX"))
    )
    (comp (ref "U10")
      (value "STTS751")
      (footprint "eagle-import:UDFN-6(2X2)")
      (libsource (lib "eagle-import") (part "STTS751"))
    )
    (comp (ref "U11")
      (value "MT3520B")
      (footprint "eagle-import:IC_SOT23-5")
      (libsource (lib "eagle-import") (part "MT3520B"))
    )
    (comp (ref "U12")
      (value "TA0281A-SAW-915MHZ")
      (footprint "eagle-import:SAW-SMD6-3_3MM")
      (libsource (lib "eagle-import") (part "TA0801A-SAW-868MHZ"))
    )
    (comp (ref "Y1")
      (value "NC")
      (footprint "eagle-import:XATL-3215-SMD")
      (libsource (lib "eagle-import") (part "XTAL-32.768KHZ"))
    )
    (comp (ref "Y2")
      (value "TCXO-32MHZ")
      (footprint "eagle-import:TXCO-SMD2.0_1.6")
      (libsource (lib "eagle-import") (part "TCXO-32MHZ"))
    )
  )
  (nets
    (net (code "1") (name "/GPIO10") (class "Default")
      (node (ref "R19") (pin "1") (pinfunction "1_1") (pintype "passive"))
      (node (ref "U1") (pin "51") (pinfunction "GPIO[10]_51") (pintype "passive"))
    )
    (net (code "2") (name "/GPIO11") (class "Default")
      (node (ref "R20") (pin "1") (pinfunction "1_1") (pintype "passive"))
      (node (ref "U1") (pin "50") (pinfunction "GPIO[11]_50") (pintype "passive"))
    )
    (net (code "3") (name "/SX1261_DIO3") (class "Default")
      (node (ref "P5") (pin "P$1") (pinfunction "P$1_P$1") (pintype "bidirectional"))
      (node (ref "U8") (pin "6") (pinfunction "DIO3_6") (pintype "bidirectional"))
    )
    (net (code "4") (name "/VR_PA") (class "Default")
      (node (ref "C26") (pin "1") (pinfunction "1_1") (pintype "passive"))
      (node (ref "C27") (pin "1") (pinfunction "1_1") (pintype "passive"))
      (node (ref "L7") (pin "2") (pinfunction "2_2") (pintype "passive"))
      (node (ref "U3") (pin "1") (pinfunction "VR_PA_1") (pintype "bidirectional"))
    )
    (net (code "5") (name "1V2") (class "Default")
      (node (ref "C76") (pin "2") (pinfunction "2_2") (pintype "passive"))
      (node (ref "C77") (pin "2") (pinfunction "2_2") (pintype "passive"))
      (node (ref "C78") (pin "2") (pinfunction "2_2") (pintype "passive"))
      (node (ref "FB3") (pin "1") (pinfunction "1_1") (pintype "passive"))
      (node (ref "L20") (pin "2") (pinfunction "2_2") (pintype "passive"))
      (node (ref "R49") (pin "1") (pinfunction "1_1") (pintype "passive"))
    )
    (net (code "6") (name "3V3_MAIN") (class "Default")
      (node (ref "C62") (pin "2") (pinfunction "2_2") (pintype "passive"))
      (node (ref "C64") (pin "2") (pinfunction "2_2") (pintype "passive"))
      (node (ref "C65") (pin "2") (pinfunction "2_2") (pintype "passive"))
      (node (ref "C68") (pin "2") (pinfunction "2_2") (pintype "passive"))
      (node (ref "C69") (pin "2") (pinfunction "2_2") (pintype "passive"))
      (node (ref "C71") (pin "2") (pinfunction "2_2") (pintype "passive"))
      (node (ref "C72") (pin "2") (pinfunction "2_2") (pintype "passive"))
      (node (ref "C73") (pin "2") (pinfunction "2_2") (pintype "passive"))
      (node (ref "C74") (pin "2") (pinfunction "2_2") (pintype "passive"))
      (node (ref "C75") (pin "2") (pinfunction "2_2") (pintype "passive"))
      (node (ref "FB5") (pin "1") (pinfunction "1_1") (pintype "passive"))
      (node (ref "FB6") (pin "1") (pinfunction "1_1") (pintype "passive"))
      (node (ref "J1") (pin "2") (pinfunction "3V3_2") (pintype "bidirectional"))
      (node (ref "J1") (pin "24") (pinfunction "3V3_24") (pintype "bidirectional"))
      (node (ref "J1") (pin "39") (pinfunction "3V3_39") (pintype "bidirectional"))
      (node (ref "J1") (pin "41") (pinfunction "3V3_41") (pintype "bidirectional"))
      (node (ref "J1") (pin "52") (pinfunction "3V3_52") (pintype "bidirectional"))
      (node (ref "P7") (pin "P$1") (pinfunction "P$1_P$1") (pintype "bidirectional"))
      (node (ref "Q1") (pin "2") (pinfunction "S_2") (pintype "passive"))
      (node (ref "R17") (pin "2") (pinfunction "2_2") (pintype "passive"))
      (node (ref "R44") (pin "2") (pinfunction "2_2") (pintype "passive"))
      (node (ref "R46") (pin "2") (pinfunction "2_2") (pintype "passive"))
      (node (ref "R47") (pin "2") (pinfunction "2_2") (pintype "passive"))
      (node (ref "R48") (pin "2") (pinfunction "2_2") (pintype "passive"))
      (node (ref "R51") (pin "1") (pinfunction "1_1") (pintype "passive"))
      (node (ref "R57") (pin "2") (pinfunction "2_2") (pintype "passive"))
      (node (ref "U10") (pin "3") (pinfunction "VDD_3") (pintype "bidirectional"))
      (node (ref "U11") (pin "1") (pinfunction "EN_1") (pintype "bidirectional"))
      (node (ref "U11") (pin "4") (pinfunction "VIN_4") (pintype "bidirectional"))
      (node (ref "U9") (pin "1") (pinfunction "VDD_1") (pintype "passive"))
      (node (ref "U9") (pin "17") (pinfunction "VDD_17") (pintype "power_in"))
      (node (ref "U9") (pin "5") (pinfunction "VDDA_5") (pintype "power_in"))
    )
    (net (code "7") (name "CONFIG_OK") (class "Default")
      (node (ref "R22") (pin "1") (pinfunction "1_1") (pintype "passive"))
      (node (ref "U1") (pin "66") (pinfunction "GPIO[0]_66") (pintype "passive"))
    )
    (net (code "8") (name "CSD") (class "Default")
      (node (ref "C51") (pin "1") (pinfunction "1_1") (pintype "passive"))
      (node (ref "R33") (pin "2") (pinfunction "2_2") (pintype "passive"))
      (node (ref "U6") (pin "4") (pinfunction "CSD_4") (pintype "input"))
    )
    (net (code "9") (name "D+") (class "Default")
      (node (ref "J1") (pin "38") (pinfunction "38_38") (pintype "bidirectional"))
      (node (ref "P2") (pin "P$1") (pinfunction "P$1_P$1") (pintype "bidirectional"))
      (node (ref "R9") (pin "1") (pinfunction "1_1") (pintype "passive"))
    )
    (net (code "10") (name "D-") (class "Default")
      (node (ref "J1") (pin "36") (pinfunction "36_36") (pintype "bidirectional"))
      (node (ref "P1") (pin "P$1") (pinfunction "P$1_P$1") (pintype "bidirectional"))
      (node (ref "R7") (pin "1") (pinfunction "1_1") (pintype "passive"))
    )
    (net (code "11") (name "GPIO6") (class "Default")
      (node (ref "U1") (pin "57") (pinfunction "GPIO[6]_57") (pintype "passive"))
    )
    (net (code "12") (name "GPIO9") (class "Default")
      (node (ref "U1") (pin "52") (pinfunction "GPIO[9]_52") (pintype "passive"))
    )
    (net (code "13") (name "HOST_CSN") (class "Default")
      (node (ref "P12") (pin "P$1") (pinfunction "P$1_P$1") (pintype "bidirectional"))
      (node (ref "R1") (pin "1") (pinfunction "1_1") (pintype "passive"))
      (node (ref "R13") (pin "1") (pinfunction "1_1") (pintype "passive"))
      (node (ref "U1") (pin "1") (pinfunction "HOST_CSN_1") (pintype "passive"))
      (node (ref "U9") (pin "10") (pinfunction "PA4_10") (pintype "bidirectional"))
    )
    (net (code "14") (name "HOST_MISO") (class "Default")
      (node (ref "P10") (pin "P$1") (pinfunction "P$1_P$1") (pintype "bidirectional"))
      (node (ref "R11") (pin "1") (pinfunction "1_1") (pintype "passive"))
      (node (ref "R2") (pin "2") (pinfunction "2_2") (pintype "passive"))
      (node (ref "R38") (pin "1") (pinfunction "1_1") (pintype "passive"))
      (node (ref "U9") (pin "12") (pinfunction "PA6_12") (pintype "bidirectional"))
    )
    (net (code "15") (name "HOST_MOSI") (class "Default")
      (node (ref "P11") (pin "P$1") (pinfunction "P$1_P$1") (pintype "bidirectional"))
      (node (ref "R12") (pin "1") (pinfunction "1_1") (pintype "passive"))
      (node (ref "U1") (pin "3") (pinfunction "HOST_MOSI_3") (pintype "passive"))
      (node (ref "U8") (pin "17") (pinfunction "MOSI_17") (pintype "bidirectional"))
      (node (ref "U9") (pin "13") (pinfunction "PA7_13") (pintype "bidirectional"))
    )
    (net (code "16") (name "HOST_SCK") (class "Default")
      (node (ref "P9") (pin "P$1") (pinfunction "P$1_P$1") (pintype "bidirectional"))
      (node (ref "R10") (pin "1") (pinfunction "1_1") (pintype "passive"))
      (node (ref "U1") (pin "4") (pinfunction "HOST_SCK_4") (pintype "passive"))
      (node (ref "U8") (pin "18") (pinfunction "SCK_18") (pintype "bidirectional"))
      (node (ref "U9") (pin "11") (pinfunction "PA5_11") (pintype "input"))
    )
    (net (code "17") (name "I2C_SCL") (class "Default")
      (node (ref "J1") (pin "30") (pinfunction "30_30") (pintype "bidirectional"))
      (node (ref "P16") (pin "P$1") (pinfunction "P$1_P$1") (pintype "bidirectional"))
      (node (ref "R47") (pin "1") (pinfunction "1_1") (pintype "passive"))
      (node (ref "U10") (pin "1") (pinfunction "SCL_1") (pintype "passive"))
      (node (ref "U9") (pin "29") (pinfunction "PB6_29") (pintype "bidirectional"))
    )
    (net (code "18") (name "I2C_SDA") (class "Default")
      (node (ref "J1") (pin "32") (pinfunction "32_32") (pintype "bidirectional"))
      (node (ref "P19") (pin "P$1") (pinfunction "P$1_P$1") (pintype "bidirectional"))
      (node (ref "R46") (pin "1") (pinfunction "1_1") (pintype "passive"))
      (node (ref "U10") (pin "6") (pinfunction "SDA_6") (pintype "bidirectional"))
      (node (ref "U9") (pin "30") (pinfunction "PB7_30") (pintype "bidirectional"))
    )
    (net (code "19") (name "MCU_NRESET") (class "Default")
      (node (ref "C80") (pin "2") (pinfunction "2_2") (pintype "passive"))
      (node (ref "P6") (pin "P$1") (pinfunction "P$1_P$1") (pintype "bidirectional"))
      (node (ref "R57") (pin "1") (pinfunction "1_1") (pintype "passive"))
      (node (ref "R58") (pin "1") (pinfunction "1_1") (pintype "passive"))
      (node (ref "U9") (pin "4") (pinfunction "NRST_4") (pintype "bidirectional"))
    )
    (net (code "20") (name "Net-(ANT1-SIGNAL)") (class "Default")
      (node (ref "ANT1") (pin "1") (pinfunction "SIGNAL_1") (pintype "bidirectional"))
      (node (ref "C47") (pin "1") (pinfunction "1_1") (pintype "passive"))
      (node (ref "D8") (pin "1") (pinfunction "1_1") (pintype "bidirectional"))
    )
    (net (code "21") (name "Net-(ANT2-SIGNAL)") (class "Default")
      (node (ref "ANT2") (pin "1") (pinfunction "SIGNAL_1") (pintype "bidirectional"))
      (node (ref "C50") (pin "1") (pinfunction "1_1") (pintype "passive"))
      (node (ref "D6") (pin "1") (pinfunction "1_1") (pintype "bidirectional"))
    )
    (net (code "22") (name "Net-(C15-Pad1)") (class "Default")
      (node (ref "C15") (pin "1") (pinfunction "1_1") (pintype "passive"))
      (node (ref "R26") (pin "1") (pinfunction "1_1") (pintype "passive"))
    )
    (net (code "23") (name "Net-(C21-Pad1)") (class "Default")
      (node (ref "C21") (pin "1") (pinfunction "1_1") (pintype "passive"))
      (node (ref "R28") (pin "1") (pinfunction "1_1") (pintype "passive"))
    )
    (net (code "24") (name "Net-(C28-Pad1)") (class "Default")
      (node (ref "C28") (pin "1") (pinfunction "1_1") (pintype "passive"))
      (node (ref "C29") (pin "1") (pinfunction "1_1") (pintype "passive"))
      (node (ref "C30") (pin "1") (pinfunction "1_1") (pintype "passive"))
      (node (ref "L8") (pin "2") (pinfunction "2_2") (pintype "passive"))
    )
    (net (code "25") (name "Net-(C30-Pad2)") (class "Default")
      (node (ref "C30") (pin "2") (pinfunction "2_2") (pintype "passive"))
      (node (ref "L9") (pin "1") (pinfunction "1_1") (pintype "passive"))
    )
    (net (code "26") (name "Net-(C40-Pad2)") (class "Default")
      (node (ref "C40") (pin "2") (pinfunction "2_2") (pintype "passive"))
      (node (ref "C41") (pin "2") (pinfunction "2_2") (pintype "passive"))
      (node (ref "L12") (pin "2") (pinfunction "2_2") (pintype "passive"))
      (node (ref "L13") (pin "1") (pinfunction "1_1") (pintype "passive"))
    )
    (net (code "27") (name "Net-(C44-Pad2)") (class "Default")
      (node (ref "C44") (pin "2") (pinfunction "2_2") (pintype "passive"))
      (node (ref "C45") (pin "1") (pinfunction "1_1") (pintype "passive"))
      (node (ref "L14") (pin "2") (pinfunction "2_2") (pintype "passive"))
      (node (ref "L15") (pin "1") (pinfunction "1_1") (pintype "passive"))
    )
    (net (code "28") (name "Net-(C46-Pad2)") (class "Default")
      (node (ref "C46") (pin "2") (pinfunction "2_2") (pintype "passive"))
      (node (ref "C47") (pin "2") (pinfunction "2_2") (pintype "passive"))
      (node (ref "L15") (pin "2") (pinfunction "2_2") (pintype "passive"))
    )
    (net (code "29") (name "Net-(C48-Pad2)") (class "Default")
      (node (ref "C48") (pin "2") (pinfunction "2_2") (pintype "passive"))
      (node (ref "L16") (pin "1") (pinfunction "1_1") (pintype "passive"))
      (node (ref "R32") (pin "2") (pinfunction "2_2") (pintype "passive"))
    )
    (net (code "30") (name "Net-(C49-Pad2)") (class "Default")
      (node (ref "C49") (pin "2") (pinfunction "2_2") (pintype "passive"))
      (node (ref "C50") (pin "2") (pinfunction "2_2") (pintype "passive"))
      (node (ref "L16") (pin "2") (pinfunction "2_2") (pintype "passive"))
    )
    (net (code "31") (name "Net-(C55-Pad1)") (class "Default")
      (node (ref "C55") (pin "1") (pinfunction "1_1") (pintype "passive"))
      (node (ref "R37") (pin "1") (pinfunction "1_1") (pintype "passive"))
    )
    (net (code "32") (name "Net-(C59-Pad1)") (class "Default")
      (node (ref "C59") (pin "1") (pinfunction "1_1") (pintype "passive"))
      (node (ref "C60") (pin "2") (pinfunction "2_2") (pintype "passive"))
      (node (ref "C61") (pin "2") (pinfunction "2_2") (pintype "passive"))
    )
    (net (code "33") (name "Net-(C63-Pad1)") (class "Default")
      (node (ref "C63") (pin "1") (pinfunction "1_1") (pintype "passive"))
      (node (ref "R54") (pin "1") (pinfunction "1_1") (pintype "passive"))
    )
    (net (code "34") (name "Net-(D1-+)") (class "Default")
      (node (ref "D1") (pin "1") (pinfunction "+_1") (pintype "passive"))
      (node (ref "R21") (pin "2") (pinfunction "2_2") (pintype "passive"))
    )
    (net (code "35") (name "Net-(D2-+)") (class "Default")
      (node (ref "D2") (pin "1") (pinfunction "+_1") (pintype "passive"))
      (node (ref "R22") (pin "2") (pinfunction "2_2") (pintype "passive"))
    )
    (net (code "36") (name "Net-(D3-+)") (class "Default")
      (node (ref "D3") (pin "1") (pinfunction "+_1") (pintype "passive"))
      (node (ref "R23") (pin "2") (pinfunction "2_2") (pintype "passive"))
    )
    (net (code "37") (name "Net-(D5-+)") (class "Default")
      (node (ref "D5") (pin "1") (pinfunction "+_1") (pintype "passive"))
      (node (ref "R51") (pin "2") (pinfunction "2_2") (pintype "passive"))
    )
    (net (code "38") (name "Net-(J1-Pad45)") (class "Default")
      (node (ref "J1") (pin "45") (pinfunction "45_45") (pintype "bidirectional"))
      (node (ref "R10") (pin "2") (pinfunction "2_2") (pintype "passive"))
    )
    (net (code "39") (name "Net-(J1-Pad47)") (class "Default")
      (node (ref "J1") (pin "47") (pinfunction "47_47") (pintype "bidirectional"))
      (node (ref "R11") (pin "2") (pinfunction "2_2") (pintype "passive"))
    )
    (net (code "40") (name "Net-(J1-Pad49)") (class "Default")
      (node (ref "J1") (pin "49") (pinfunction "49_49") (pintype "bidirectional"))
      (node (ref "R12") (pin "2") (pinfunction "2_2") (pintype "passive"))
    )
    (net (code "41") (name "Net-(J1-Pad51)") (class "Default")
      (node (ref "J1") (pin "51") (pinfunction "51_51") (pintype "bidirectional"))
      (node (ref "R13") (pin "2") (pinfunction "2_2") (pintype "passive"))
    )
    (net (code "42") (name "Net-(Q1-G)") (class "Default")
      (node (ref "Q1") (pin "1") (pinfunction "G_1") (pintype "passive"))
      (node (ref "Q2") (pin "3") (pinfunction "D_3") (pintype "passive"))
      (node (ref "R17") (pin "1") (pinfunction "1_1") (pintype "passive"))
    )
    (net (code "43") (name "Net-(Q2-G)") (class "Default")
      (node (ref "Q2") (pin "1") (pinfunction "G_1") (pintype "passive"))
      (node (ref "R18") (pin "1") (pinfunction "1_1") (pintype "passive"))
      (node (ref "R52") (pin "1") (pinfunction "1_1") (pintype "passive"))
    )
    (net (code "44") (name "Net-(U1-HOST_MISO)") (class "Default")
      (node (ref "R2") (pin "1") (pinfunction "1_1") (pintype "passive"))
      (node (ref "U1") (pin "2") (pinfunction "HOST_MISO_2") (pintype "passive"))
    )
    (net (code "45") (name "Net-(U1-RADIO_A_CLK_I)") (class "Default")
      (node (ref "R14") (pin "1") (pinfunction "1_1") (pintype "passive"))
      (node (ref "U1") (pin "43") (pinfunction "RADIO_A_CLK_I_43") (pintype "passive"))
    )
    (net (code "46") (name "Net-(U1-RADIO_B_CLK_I)") (class "Default")
      (node (ref "R8") (pin "1") (pinfunction "1_1") (pintype "passive"))
      (node (ref "U1") (pin "34") (pinfunction "RADIO_B_CLK_I_34") (pintype "passive"))
    )
    (net (code "47") (name "Net-(U2-DCC_SW)") (class "Default")
      (node (ref "L1") (pin "2") (pinfunction "2_2") (pintype "passive"))
      (node (ref "U2") (pin "8") (pinfunction "DCC_SW_8") (pintype "bidirectional"))
    )
    (net (code "48") (name "Net-(U2-RFI_N)") (class "Default")
      (node (ref "C19") (pin "2") (pinfunction "2_2") (pintype "passive"))
      (node (ref "L3") (pin "2") (pinfunction "2_2") (pintype "passive"))
      (node (ref "U2") (pin "23") (pinfunction "RFI_N_23") (pintype "bidirectional"))
    )
    (net (code "49") (name "Net-(U2-RFI_P)") (class "Default")
      (node (ref "C18") (pin "2") (pinfunction "2_2") (pintype "passive"))
      (node (ref "L3") (pin "1") (pinfunction "1_1") (pintype "passive"))
      (node (ref "U2") (pin "22") (pinfunction "RFI_P_22") (pintype "bidirectional"))
    )
    (net (code "50") (name "Net-(U2-VDD_IN)") (class "Default")
      (node (ref "C14") (pin "1") (pinfunction "1_1") (pintype "passive"))
      (node (ref "L2") (pin "2") (pinfunction "2_2") (pintype "passive"))
      (node (ref "R25") (pin "1") (pinfunction "1_1") (pintype "passive"))
      (node (ref "U2") (pin "2") (pinfunction "VDD_IN_2") (pintype "bidirectional"))
    )
    (net (code "51") (name "Net-(U2-VREG)") (class "Default")
      (node (ref "C16") (pin "1") (pinfunction "1_1") (pintype "passive"))
      (node (ref "L1") (pin "1") (pinfunction "1_1") (pintype "passive"))
      (node (ref "L2") (pin "1") (pinfunction "1_1") (pintype "passive"))
      (node (ref "U2") (pin "6") (pinfunction "VREG_6") (pintype "bidirectional"))
    )
    (net (code "52") (name "Net-(U2-XTA)") (class "Default")
      (node (ref "C15") (pin "2") (pinfunction "2_2") (pintype "passive"))
      (node (ref "U2") (pin "3") (pinfunction "XTA_3") (pintype "bidirectional"))
    )
    (net (code "53") (name "Net-(U3-DCC_SW)") (class "Default")
      (node (ref "L4") (pin "2") (pinfunction "2_2") (pintype "passive"))
      (node (ref "U3") (pin "8") (pinfunction "DCC_SW_8") (pintype "bidirectional"))
    )
    (net (code "54") (name "Net-(U3-RFI_N)") (class "Default")
      (node (ref "C25") (pin "2") (pinfunction "2_2") (pintype "passive"))
      (node (ref "L6") (pin "2") (pinfunction "2_2") (pintype "passive"))
      (node (ref "U3") (pin "23") (pinfunction "RFI_N_23") (pintype "bidirectional"))
    )
    (net (code "55") (name "Net-(U3-RFI_P)") (class "Default")
      (node (ref "C24") (pin "2") (pinfunction "2_2") (pintype "passive"))
      (node (ref "L6") (pin "1") (pinfunction "1_1") (pintype "passive"))
      (node (ref "U3") (pin "22") (pinfunction "RFI_P_22") (pintype "bidirectional"))
    )
    (net (code "56") (name "Net-(U3-RFO)") (class "Default")
      (node (ref "C28") (pin "2") (pinfunction "2_2") (pintype "passive"))
      (node (ref "L7") (pin "1") (pinfunction "1_1") (pintype "passive"))
      (node (ref "L8") (pin "1") (pinfunction "1_1") (pintype "passive"))
      (node (ref "U3") (pin "24") (pinfunction "RFO_24") (pintype "bidirectional"))
    )
    (net (code "57") (name "Net-(U3-VDD_IN)") (class "Default")
      (node (ref "C20") (pin "1") (pinfunction "1_1") (pintype "passive"))
      (node (ref "L5") (pin "2") (pinfunction "2_2") (pintype "passive"))
      (node (ref "R27") (pin "1") (pinfunction "1_1") (pintype "passive"))
      (node (ref "U3") (pin "2") (pinfunction "VDD_IN_2") (pintype "bidirectional"))
    )
    (net (code "58") (name "Net-(U3-VREG)") (class "Default")
      (node (ref "C22") (pin "1") (pinfunction "1_1") (pintype "passive"))
      (node (ref "L4") (pin "1") (pinfunction "1_1") (pintype "passive"))
      (node (ref "L5") (pin "1") (pinfunction "1_1") (pintype "passive"))
      (node (ref "U3") (pin "6") (pinfunction "VREG_6") (pintype "bidirectional"))
    )
    (net (code "59") (name "Net-(U3-XTA)") (class "Default")
      (node (ref "C21") (pin "2") (pinfunction "2_2") (pintype "passive"))
      (node (ref "U3") (pin "3") (pinfunction "XTA_3") (pintype "bidirectional"))
    )
    (net (code "60") (name "Net-(U4-IN{slash}OUT)") (class "Default")
      (node (ref "C34") (pin "1") (pinfunction "1_1") (pintype "passive"))
      (node (ref "U4") (pin "2") (pinfunction "IN/OUT_2") (pintype "bidirectional"))
    )
    (net (code "61") (name "Net-(U4-OUT{slash}IN)") (class "Default")
      (node (ref "C19") (pin "1") (pinfunction "1_1") (pintype "passive"))
      (node (ref "C25") (pin "1") (pinfunction "1_1") (pintype "passive"))
      (node (ref "C61") (pin "1") (pinfunction "1_1") (pintype "passive"))
      (node (ref "U4") (pin "5") (pinfunction "OUT/IN_5") (pintype "bidirectional"))
    )
    (net (code "62") (name "Net-(U5-IN{slash}OUT)") (class "Default")
      (node (ref "R31") (pin "2") (pinfunction "2_2") (pintype "passive"))
      (node (ref "R32") (pin "1") (pinfunction "1_1") (pintype "passive"))
      (node (ref "U5") (pin "2") (pinfunction "IN/OUT_2") (pintype "bidirectional"))
    )
    (net (code "63") (name "Net-(U5-OUT{slash}IN)") (class "Default")
      (node (ref "U5") (pin "5") (pinfunction "OUT/IN_5") (pintype "bidirectional"))
      (node (ref "U6") (pin "7") (pinfunction "LNA_IN_7") (pintype "passive"))
    )
    (net (code "64") (name "Net-(U6-ANT)") (class "Default")
      (node (ref "C43") (pin "2") (pinfunction "2_2") (pintype "passive"))
      (node (ref "C45") (pin "2") (pinfunction "2_2") (pintype "passive"))
      (node (ref "L14") (pin "1") (pinfunction "1_1") (pintype "passive"))
      (node (ref "U6") (pin "9") (pinfunction "ANT_9") (pintype "passive"))
    )
    (net (code "65") (name "Net-(U6-PA_OUT)") (class "Default")
      (node (ref "L11") (pin "1") (pinfunction "1_1") (pintype "passive"))
      (node (ref "L12") (pin "1") (pinfunction "1_1") (pintype "passive"))
      (node (ref "U6") (pin "13") (pinfunction "PA_OUT_13") (pintype "passive"))
    )
    (net (code "66") (name "Net-(U6-RX)") (class "Default")
      (node (ref "C34") (pin "2") (pinfunction "2_2") (pintype "passive"))
      (node (ref "U6") (pin "2") (pinfunction "RX_2") (pintype "passive"))
    )
    (net (code "67") (name "Net-(U6-RX_FLT)") (class "Default")
      (node (ref "R31") (pin "1") (pinfunction "1_1") (pintype "passive"))
      (node (ref "U6") (pin "8") (pinfunction "RX_FLT_8") (pintype "passive"))
    )
    (net (code "68") (name "Net-(U6-TX)") (class "Default")
      (node (ref "C33") (pin "2") (pinfunction "2_2") (pintype "passive"))
      (node (ref "U6") (pin "1") (pinfunction "TX_1") (pintype "passive"))
    )
    (net (code "69") (name "Net-(U6-TX_IN)") (class "Default")
      (node (ref "C42") (pin "2") (pinfunction "2_2") (pintype "passive"))
      (node (ref "L13") (pin "2") (pinfunction "2_2") (pintype "passive"))
      (node (ref "U6") (pin "11") (pinfunction "TX_IN_11") (pintype "passive"))
    )
    (net (code "70") (name "Net-(U6-VCC1)") (class "Default")
      (node (ref "L10") (pin "1") (pinfunction "1_1") (pintype "passive"))
      (node (ref "U6") (pin "16") (pinfunction "VCC1_16") (pintype "power_in"))
    )
    (net (code "71") (name "Net-(U8-DCC_SW)") (class "Default")
      (node (ref "L18") (pin "2") (pinfunction "2_2") (pintype "passive"))
      (node (ref "U8") (pin "9") (pinfunction "DCC_SW_9") (pintype "bidirectional"))
    )
    (net (code "72") (name "Net-(U8-MISO)") (class "Default")
      (node (ref "R38") (pin "2") (pinfunction "2_2") (pintype "passive"))
      (node (ref "U8") (pin "16") (pinfunction "MISO_16") (pintype "bidirectional"))
    )
    (net (code "73") (name "Net-(U8-NSS)") (class "Default")
      (node (ref "R41") (pin "2") (pinfunction "2_2") (pintype "passive"))
      (node (ref "U8") (pin "19") (pinfunction "NSS_19") (pintype "bidirectional"))
    )
    (net (code "74") (name "Net-(U8-RFI_N)") (class "Default")
      (node (ref "C59") (pin "2") (pinfunction "2_2") (pintype "passive"))
      (node (ref "L19") (pin "2") (pinfunction "2_2") (pintype "passive"))
      (node (ref "U8") (pin "22") (pinfunction "RFI_N_22") (pintype "bidirectional"))
    )
    (net (code "75") (name "Net-(U8-RFI_P)") (class "Default")
      (node (ref "C58") (pin "2") (pinfunction "2_2") (pintype "passive"))
      (node (ref "L19") (pin "1") (pinfunction "1_1") (pintype "passive"))
      (node (ref "U8") (pin "21") (pinfunction "RFI_P_21") (pintype "bidirectional"))
    )
    (net (code "76") (name "Net-(U8-VDD_IN)") (class "Default")
      (node (ref "C54") (pin "1") (pinfunction "1_1") (pintype "passive"))
      (node (ref "L17") (pin "2") (pinfunction "2_2") (pintype "passive"))
      (node (ref "R36") (pin "1") (pinfunction "1_1") (pintype "passive"))
      (node (ref "U8") (pin "1") (pinfunction "VDD_IN_1") (pintype "bidirectional"))
    )
    (net (code "77") (name "Net-(U8-VREG)") (class "Default")
      (node (ref "C56") (pin "1") (pinfunction "1_1") (pintype "passive"))
      (node (ref "L17") (pin "1") (pinfunction "1_1") (pintype "passive"))
      (node (ref "L18") (pin "1") (pinfunction "1_1") (pintype "passive"))
      (node (ref "U8") (pin "7") (pinfunction "VREG_7") (pintype "bidirectional"))
    )
    (net (code "78") (name "Net-(U8-XTA)") (class "Default")
      (node (ref "C55") (pin "2") (pinfunction "2_2") (pintype "passive"))
      (node (ref "U8") (pin "3") (pinfunction "XTA_3") (pintype "bidirectional"))
    )
    (net (code "79") (name "Net-(U9-BOOT)") (class "Default")
      (node (ref "R44") (pin "1") (pinfunction "1_1") (pintype "passive"))
      (node (ref "R45") (pin "2") (pinfunction "2_2") (pintype "passive"))
      (node (ref "U9") (pin "31") (pinfunction "BOOT_31") (pintype "bidirectional"))
    )
    (net (code "80") (name "Net-(U9-PA0-CK_IN)") (class "Default")
      (node (ref "R42") (pin "2") (pinfunction "2_2") (pintype "passive"))
      (node (ref "R43") (pin "1") (pinfunction "1_1") (pintype "passive"))
      (node (ref "U9") (pin "6") (pinfunction "PA0-CK_IN_6") (pintype "bidirectional"))
    )
    (net (code "81") (name "Net-(U9-PC14-OSC32_IN)") (class "Default")
      (node (ref "C66") (pin "2") (pinfunction "2_2") (pintype "passive"))
      (node (ref "U9") (pin "2") (pinfunction "PC14-OSC32_IN_2") (pintype "bidirectional"))
      (node (ref "Y1") (pin "2") (pinfunction "2_2") (pintype "bidirectional"))
    )
    (net (code "82") (name "Net-(U9-PC15-OSC32_OUT)") (class "Default")
      (node (ref "C67") (pin "1") (pinfunction "1_1") (pintype "passive"))
      (node (ref "U9") (pin "3") (pinfunction "PC15-OSC32_OUT_3") (pintype "bidirectional"))
      (node (ref "Y1") (pin "1") (pinfunction "1_1") (pintype "bidirectional"))
    )
    (net (code "83") (name "Net-(U10-\\E\\V\\E\\N\\T\\)") (class "Default")
      (node (ref "R48") (pin "1") (pinfunction "1_1") (pintype "passive"))
      (node (ref "U10") (pin "2") (pinfunction "\\E\\V\\E\\N\\T\\_2") (pintype "passive"))
    )
    (net (code "84") (name "Net-(U11-FB)") (class "Default")
      (node (ref "R49") (pin "2") (pinfunction "2_2") (pintype "passive"))
      (node (ref "R50") (pin "1") (pinfunction "1_1") (pintype "passive"))
      (node (ref "U11") (pin "5") (pinfunction "FB_5") (pintype "bidirectional"))
    )
    (net (code "85") (name "Net-(U11-SW)") (class "Default")
      (node (ref "L20") (pin "1") (pinfunction "1_1") (pintype "passive"))
      (node (ref "U11") (pin "3") (pinfunction "SW_3") (pintype "bidirectional"))
    )
    (net (code "86") (name "Net-(U12-IN{slash}OUT)") (class "Default")
      (node (ref "C31") (pin "1") (pinfunction "1_1") (pintype "passive"))
      (node (ref "L9") (pin "2") (pinfunction "2_2") (pintype "passive"))
      (node (ref "U12") (pin "2") (pinfunction "IN/OUT_2") (pintype "bidirectional"))
    )
    (net (code "87") (name "Net-(U12-OUT{slash}IN)") (class "Default")
      (node (ref "C33") (pin "1") (pinfunction "1_1") (pintype "passive"))
      (node (ref "U12") (pin "5") (pinfunction "OUT/IN_5") (pintype "bidirectional"))
    )
    (net (code "88") (name "Net-(Y2-OUT)") (class "Default")
      (node (ref "R24") (pin "1") (pinfunction "1_1") (pintype "passive"))
      (node (ref "Y2") (pin "3") (pinfunction "OUT_3") (pintype "bidirectional"))
    )
    (net (code "89") (name "Net-(Y2-VCC)") (class "Default")
      (node (ref "C13") (pin "2") (pinfunction "2_2") (pintype "passive"))
      (node (ref "FB1") (pin "2") (pinfunction "2_2") (pintype "passive"))
      (node (ref "Y2") (pin "4") (pinfunction "VCC_4") (pintype "bidirectional"))
    )
    (net (code "90") (name "PA_ON") (class "Default")
      (node (ref "C53") (pin "1") (pinfunction "1_1") (pintype "passive"))
      (node (ref "R35") (pin "2") (pinfunction "2_2") (pintype "passive"))
      (node (ref "U6") (pin "5") (pinfunction "CPS_5") (pintype "input"))
    )
    (net (code "91") (name "POWER_EN") (class "Default")
      (node (ref "U9") (pin "7") (pinfunction "PA1_7") (pintype "bidirectional"))
    )
    (net (code "92") (name "POWER_GND") (class "Default")
      (node (ref "ANT1") (pin "2") (pinfunction "GND_2") (pintype "bidirectional"))
      (node (ref "ANT1") (pin "3") (pinfunction "GND_3") (pintype "bidirectional"))
      (node (ref "ANT2") (pin "2") (pinfunction "GND_2") (pintype "bidirectional"))
      (node (ref "ANT2") (pin "3") (pinfunction "GND_3") (pintype "bidirectional"))
      (node (ref "C1") (pin "1") (pinfunction "1_1") (pintype "passive"))
      (node (ref "C10") (pin "1") (pinfunction "1_1") (pintype "passive"))
      (node (ref "C11") (pin "1") (pinfunction "1_1") (pintype "passive"))
      (node (ref "C12") (pin "1") (pinfunction "1_1") (pintype "passive"))
      (node (ref "C13") (pin "1") (pinfunction "1_1") (pintype "passive"))
      (node (ref "C14") (pin "2") (pinfunction "2_2") (pintype "passive"))
      (node (ref "C16") (pin "2") (pinfunction "2_2") (pintype "passive"))
      (node (ref "C17") (pin "1") (pinfunction "1_1") (pintype "passive"))
      (node (ref "C18") (pin "1") (pinfunction "1_1") (pintype "passive"))
      (node (ref "C2") (pin "1") (pinfunction "1_1") (pintype "passive"))
      (node (ref "C20") (pin "2") (pinfunction "2_2") (pintype "passive"))
      (node (ref "C22") (pin "2") (pinfunction "2_2") (pintype "passive"))
      (node (ref "C23") (pin "1") (pinfunction "1_1") (pintype "passive"))
      (node (ref "C24") (pin "1") (pinfunction "1_1") (pintype "passive"))
      (node (ref "C26") (pin "2") (pinfunction "2_2") (pintype "passive"))
      (node (ref "C27") (pin "2") (pinfunction "2_2") (pintype "passive"))
      (node (ref "C29") (pin "2") (pinfunction "2_2") (pintype "passive"))
      (node (ref "C3") (pin "1") (pinfunction "1_1") (pintype "passive"))
      (node (ref "C31") (pin "2") (pinfunction "2_2") (pintype "passive"))
      (node (ref "C35") (pin "1") (pinfunction "1_1") (pintype "passive"))
      (node (ref "C36") (pin "1") (pinfunction "1_1") (pintype "passive"))
      (node (ref "C37") (pin "1") (pinfunction "1_1") (pintype "passive"))
      (node (ref "C38") (pin "1") (pinfunction "1_1") (pintype "passive"))
      (node (ref "C39") (pin "1") (pinfunction "1_1") (pintype "passive"))
      (node (ref "C4") (pin "1") (pinfunction "1_1") (pintype "passive"))
      (node (ref "C40") (pin "1") (pinfunction "1_1") (pintype "passive"))
      (node (ref "C41") (pin "1") (pinfunction "1_1") (pintype "passive"))
      (node (ref "C42") (pin "1") (pinfunction "1_1") (pintype "passive"))
      (node (ref "C43") (pin "1") (pinfunction "1_1") (pintype "passive"))
      (node (ref "C44") (pin "1") (pinfunction "1_1") (pintype "passive"))
      (node (ref "C46") (pin "1") (pinfunction "1_1") (pintype "passive"))
      (node (ref "C48") (pin "1") (pinfunction "1_1") (pintype "passive"))
      (node (ref "C49") (pin "1") (pinfunction "1_1") (pintype "passive"))
      (node (ref "C5") (pin "1") (pinfunction "1_1") (pintype "passive"))
      (node (ref "C51") (pin "2") (pinfunction "2_2") (pintype "passive"))
      (node (ref "C52") (pin "2") (pinfunction "2_2") (pintype "passive"))
      (node (ref "C53") (pin "2") (pinfunction "2_2") (pintype "passive"))
      (node (ref "C54") (pin "2") (pinfunction "2_2") (pintype "passive"))
      (node (ref "C56") (pin "2") (pinfunction "2_2") (pintype "passive"))
      (node (ref "C57") (pin "1") (pinfunction "1_1") (pintype "passive"))
      (node (ref "C58") (pin "1") (pinfunction "1_1") (pintype "passive"))
      (node (ref "C6") (pin "1") (pinfunction "1_1") (pintype "passive"))
      (node (ref "C60") (pin "1") (pinfunction "1_1") (pintype "passive"))
      (node (ref "C62") (pin "1") (pinfunction "1_1") (pintype "passive"))
      (node (ref "C64") (pin "1") (pinfunction "1_1") (pintype "passive"))
      (node (ref "C65") (pin "1") (pinfunction "1_1") (pintype "passive"))
      (node (ref "C66") (pin "1") (pinfunction "1_1") (pintype "passive"))
      (node (ref "C67") (pin "2") (pinfunction "2_2") (pintype "passive"))
      (node (ref "C68") (pin "1") (pinfunction "1_1") (pintype "passive"))
      (node (ref "C69") (pin "1") (pinfunction "1_1") (pintype "passive"))
      (node (ref "C7") (pin "1") (pinfunction "1_1") (pintype "passive"))
      (node (ref "C71") (pin "1") (pinfunction "1_1") (pintype "passive"))
      (node (ref "C72") (pin "1") (pinfunction "1_1") (pintype "passive"))
      (node (ref "C73") (pin "1") (pinfunction "1_1") (pintype "passive"))
      (node (ref "C74") (pin "1") (pinfunction "1_1") (pintype "passive"))
      (node (ref "C75") (pin "1") (pinfunction "1_1") (pintype "passive"))
      (node (ref "C76") (pin "1") (pinfunction "1_1") (pintype "passive"))
      (node (ref "C77") (pin "1") (pinfunction "1_1") (pintype "passive"))
      (node (ref "C78") (pin "1") (pinfunction "1_1") (pintype "passive"))
      (node (ref "C79") (pin "1") (pinfunction "1_1") (pintype "passive"))
      (node (ref "C8") (pin "1") (pinfunction "1_1") (pintype "passive"))
      (node (ref "C80") (pin "1") (pinfunction "1_1") (pintype "passive"))
      (node (ref "C81") (pin "1") (pinfunction "1_1") (pintype "passive"))
      (node (ref "C82") (pin "1") (pinfunction "1_1") (pintype "passive"))
      (node (ref "C83") (pin "1") (pinfunction "1_1") (pintype "passive"))
      (node (ref "C84") (pin "1") (pinfunction "1_1") (pintype "passive"))
      (node (ref "C9") (pin "1") (pinfunction "1_1") (pintype "passive"))
      (node (ref "D1") (pin "2") (pinfunction "-_2") (pintype "passive"))
      (node (ref "D2") (pin "2") (pinfunction "-_2") (pintype "passive"))
      (node (ref "D3") (pin "2") (pinfunction "-_2") (pintype "passive"))
      (node (ref "D5") (pin "2") (pinfunction "-_2") (pintype "passive"))
      (node (ref "D6") (pin "2") (pinfunction "2_2") (pintype "bidirectional"))
      (node (ref "D8") (pin "2") (pinfunction "2_2") (pintype "bidirectional"))
      (node (ref "J1") (pin "15") (pinfunction "GND_15") (pintype "bidirectional"))
      (node (ref "J1") (pin "18") (pinfunction "GND_18") (pintype "bidirectional"))
      (node (ref "J1") (pin "21") (pinfunction "GND_21") (pintype "bidirectional"))
      (node (ref "J1") (pin "26") (pinfunction "GND_26") (pintype "bidirectional"))
      (node (ref "J1") (pin "27") (pinfunction "GND_27") (pintype "bidirectional"))
      (node (ref "J1") (pin "29") (pinfunction "GND_29") (pintype "bidirectional"))
      (node (ref "J1") (pin "34") (pinfunction "GND_34") (pintype "bidirectional"))
      (node (ref "J1") (pin "35") (pinfunction "GND_35") (pintype "bidirectional"))
      (node (ref "J1") (pin "37") (pinfunction "GND_37") (pintype "bidirectional"))
      (node (ref "J1") (pin "4") (pinfunction "GND_4") (pintype "bidirectional"))
      (node (ref "J1") (pin "40") (pinfunction "GND_40") (pintype "bidirectional"))
      (node (ref "J1") (pin "43") (pinfunction "GND_43") (pintype "bidirectional"))
      (node (ref "J1") (pin "50") (pinfunction "GND_50") (pintype "bidirectional"))
      (node (ref "J1") (pin "9") (pinfunction "GND_9") (pintype "bidirectional"))
      (node (ref "J10") (pin "1") (pinfunction "1_1") (pintype "bidirectional"))
      (node (ref "J10") (pin "2") (pinfunction "2_2") (pintype "bidirectional"))
      (node (ref "J10") (pin "3") (pinfunction "3_3") (pintype "bidirectional"))
      (node (ref "J11") (pin "1") (pinfunction "P$1_1") (pintype "bidirectional"))
      (node (ref "J17") (pin "1") (pinfunction "1_1") (pintype "bidirectional"))
      (node (ref "J17") (pin "2") (pinfunction "2_2") (pintype "bidirectional"))
      (node (ref "J17") (pin "3") (pinfunction "3_3") (pintype "bidirectional"))
      (node (ref "J2") (pin "1") (pinfunction "P$1_1") (pintype "bidirectional"))
      (node (ref "J3") (pin "1") (pinfunction "1_1") (pintype "bidirectional"))
      (node (ref "J3") (pin "2") (pinfunction "2_2") (pintype "bidirectional"))
      (node (ref "J3") (pin "3") (pinfunction "3_3") (pintype "bidirectional"))
      (node (ref "J4") (pin "1") (pinfunction "1_1") (pintype "bidirectional"))
      (node (ref "J4") (pin "2") (pinfunction "2_2") (pintype "bidirectional"))
      (node (ref "J4") (pin "3") (pinfunction "3_3") (pintype "bidirectional"))
      (node (ref "J5") (pin "1") (pinfunction "1_1") (pintype "bidirectional"))
      (node (ref "J5") (pin "2") (pinfunction "2_2") (pintype "bidirectional"))
      (node (ref "J5") (pin "3") (pinfunction "3_3") (pintype "bidirectional"))
      (node (ref "J6") (pin "1") (pinfunction "1_1") (pintype "bidirectional"))
      (node (ref "J6") (pin "2") (pinfunction "2_2") (pintype "bidirectional"))
      (node (ref "J6") (pin "3") (pinfunction "3_3") (pintype "bidirectional"))
      (node (ref "J7") (pin "1") (pinfunction "1_1") (pintype "bidirectional"))
      (node (ref "J7") (pin "2") (pinfunction "2_2") (pintype "bidirectional"))
      (node (ref "J7") (pin "3") (pinfunction "3_3") (pintype "bidirectional"))
      (node (ref "P24") (pin "P$1") (pinfunction "P$1_P$1") (pintype "bidirectional"))
      (node (ref "P8") (pin "P$1") (pinfunction "P$1_P$1") (pintype "bidirectional"))
      (node (ref "Q2") (pin "2") (pinfunction "S_2") (pintype "passive"))
      (node (ref "R15") (pin "1") (pinfunction "1_1") (pintype "passive"))
      (node (ref "R15") (pin "2") (pinfunction "2_2") (pintype "passive"))
      (node (ref "R16") (pin "1") (pinfunction "1_1") (pintype "passive"))
      (node (ref "R16") (pin "2") (pinfunction "2_2") (pintype "passive"))
      (node (ref "R3") (pin "1") (pinfunction "1_1") (pintype "passive"))
      (node (ref "R3") (pin "2") (pinfunction "2_2") (pintype "passive"))
      (node (ref "R43") (pin "2") (pinfunction "2_2") (pintype "passive"))
      (node (ref "R45") (pin "1") (pinfunction "1_1") (pintype "passive"))
      (node (ref "R5") (pin "1") (pinfunction "1_1") (pintype "passive"))
      (node (ref "R50") (pin "2") (pinfunction "2_2") (pintype "passive"))
      (node (ref "R52") (pin "2") (pinfunction "2_2") (pintype "passive"))
      (node (ref "R53") (pin "1") (pinfunction "1_1") (pintype "passive"))
      (node (ref "R53") (pin "2") (pinfunction "2_2") (pintype "passive"))
      (node (ref "U1") (pin "15") (pinfunction "GND_15") (pintype "power_in"))
      (node (ref "U1") (pin "20") (pinfunction "SP_VALID_20") (pintype "passive"))
      (node (ref "U1") (pin "24") (pinfunction "GND_24") (pintype "power_in"))
      (node (ref "U1") (pin "25") (pinfunction "GND_25") (pintype "power_in"))
      (node (ref "U1") (pin "39") (pinfunction "GND_39") (pintype "power_in"))
      (node (ref "U1") (pin "46") (pinfunction "GND_46") (pintype "power_in"))
      (node (ref "U1") (pin "55") (pinfunction "GND_55") (pintype "power_in"))
      (node (ref "U1") (pin "6") (pinfunction "GND_6") (pintype "power_in"))
      (node (ref "U1") (pin "62") (pinfunction "GND_62") (pintype "power_in"))
      (node (ref "U1") (pin "69") (pinfunction "GND_69") (pintype "power_in"))
      (node (ref "U1") (pin "9") (pinfunction "GND_9") (pintype "passive"))
      (node (ref "U10") (pin "4") (pinfunction "ADDR/T\\H\\E\\R\\M\\_4") (pintype "passive"))
      (node (ref "U10") (pin "5") (pinfunction "GND_5") (pintype "bidirectional"))
      (node (ref "U11") (pin "2") (pinfunction "GND_2") (pintype "bidirectional"))
      (node (ref "U12") (pin "1") (pinfunction "GND_1") (pintype "bidirectional"))
      (node (ref "U12") (pin "3") (pinfunction "GND_3") (pintype "bidirectional"))
      (node (ref "U12") (pin "4") (pinfunction "GND_4") (pintype "bidirectional"))
      (node (ref "U12") (pin "6") (pinfunction "GND_6") (pintype "bidirectional"))
      (node (ref "U2") (pin "20") (pinfunction "GND_20") (pintype "bidirectional"))
      (node (ref "U2") (pin "25") (pinfunction "GND_25") (pintype "power_in"))
      (node (ref "U2") (pin "7") (pinfunction "GND_7") (pintype "power_in"))
      (node (ref "U3") (pin "20") (pinfunction "GND_20") (pintype "bidirectional"))
      (node (ref "U3") (pin "25") (pinfunction "GND_25") (pintype "power_in"))
      (node (ref "U3") (pin "7") (pinfunction "GND_7") (pintype "power_in"))
      (node (ref "U4") (pin "1") (pinfunction "GND_1") (pintype "bidirectional"))
      (node (ref "U4") (pin "3") (pinfunction "GND_3") (pintype "bidirectional"))
      (node (ref "U4") (pin "4") (pinfunction "GND_4") (pintype "bidirectional"))
      (node (ref "U4") (pin "6") (pinfunction "GND_6") (pintype "bidirectional"))
      (node (ref "U5") (pin "1") (pinfunction "GND_1") (pintype "bidirectional"))
      (node (ref "U5") (pin "3") (pinfunction "GND_3") (pintype "bidirectional"))
      (node (ref "U5") (pin "4") (pinfunction "GND_4") (pintype "bidirectional"))
      (node (ref "U5") (pin "6") (pinfunction "GND_6") (pintype "bidirectional"))
      (node (ref "U6") (pin "10") (pinfunction "GND_10") (pintype "power_in"))
      (node (ref "U6") (pin "12") (pinfunction "GND_12") (pintype "power_in"))
      (node (ref "U6") (pin "17") (pinfunction "GND_17") (pintype "power_in"))
      (node (ref "U8") (pin "2") (pinfunction "GND_2") (pintype "bidirectional"))
      (node (ref "U8") (pin "20") (pinfunction "GND_20") (pintype "bidirectional"))
      (node (ref "U8") (pin "25") (pinfunction "GND_25") (pintype "bidirectional"))
      (node (ref "U8") (pin "5") (pinfunction "GND_5") (pintype "bidirectional"))
      (node (ref "U8") (pin "8") (pinfunction "GND_8") (pintype "bidirectional"))
      (node (ref "U9") (pin "16") (pinfunction "VSS_16") (pintype "power_in"))
      (node (ref "U9") (pin "32") (pinfunction "VSS_32") (pintype "power_in"))
      (node (ref "U9") (pin "33") (pinfunction "VSS_33") (pintype "power_in"))
      (node (ref "Y2") (pin "1") (pinfunction "GND_1") (pintype "bidirectional"))
      (node (ref "Y2") (pin "2") (pinfunction "GND_2") (pintype "bidirectional"))
    )
    (net (code "93") (name "PPS") (class "Default")
      (node (ref "J1") (pin "19") (pinfunction "19_19") (pintype "bidirectional"))
      (node (ref "P21") (pin "P$1") (pinfunction "P$1_P$1") (pintype "bidirectional"))
      (node (ref "U1") (pin "8") (pinfunction "PPS_8") (pintype "passive"))
      (node (ref "U9") (pin "27") (pinfunction "PB4_27") (pintype "bidirectional"))
    )
    (net (code "94") (name "P_RESET") (class "Default")
      (node (ref "D4") (pin "+") (pinfunction "+_+") (pintype "passive"))
      (node (ref "J1") (pin "22") (pinfunction "22_22") (pintype "bidirectional"))
      (node (ref "P20") (pin "P$1") (pinfunction "P$1_P$1") (pintype "bidirectional"))
      (node (ref "R58") (pin "2") (pinfunction "2_2") (pintype "passive"))
    )
    (net (code "95") (name "RADIO_A_CLK_32M") (class "Default")
      (node (ref "R14") (pin "2") (pinfunction "2_2") (pintype "passive"))
      (node (ref "R42") (pin "1") (pinfunction "1_1") (pintype "passive"))
      (node (ref "U3") (pin "14") (pinfunction "BUSY_14") (pintype "bidirectional"))
    )
    (net (code "96") (name "RADIO_A_CLK_O") (class "Default")
      (node (ref "U1") (pin "48") (pinfunction "RADIO_A_IQ[4]_48") (pintype "passive"))
      (node (ref "U3") (pin "11") (pinfunction "DIO5_11") (pintype "bidirectional"))
    )
    (net (code "97") (name "RADIO_A_CSN") (class "Default")
      (node (ref "U1") (pin "68") (pinfunction "RADIO_A_CSN_68") (pintype "passive"))
      (node (ref "U3") (pin "19") (pinfunction "NSS_19") (pintype "bidirectional"))
    )
    (net (code "98") (name "RADIO_A_IQ0") (class "Default")
      (node (ref "U1") (pin "44") (pinfunction "RADIO_A_IQ[0]_44") (pintype "passive"))
      (node (ref "U3") (pin "13") (pinfunction "DIO1_13") (pintype "bidirectional"))
    )
    (net (code "99") (name "RADIO_A_IQ1") (class "Default")
      (node (ref "U1") (pin "45") (pinfunction "RADIO_A_IQ[1]_45") (pintype "passive"))
      (node (ref "U3") (pin "12") (pinfunction "DIO2_12") (pintype "bidirectional"))
    )
    (net (code "100") (name "RADIO_A_IQ2") (class "Default")
      (node (ref "U1") (pin "49") (pinfunction "RADIO_A_IQ[2]_49") (pintype "passive"))
      (node (ref "U3") (pin "5") (pinfunction "DIO3_5") (pintype "bidirectional"))
    )
    (net (code "101") (name "RADIO_A_IQ3") (class "Default")
      (node (ref "U1") (pin "41") (pinfunction "RADIO_A_IQ[3]_41") (pintype "passive"))
      (node (ref "U3") (pin "21") (pinfunction "DIO4_21") (pintype "bidirectional"))
    )
    (net (code "102") (name "RADIO_A_MISO") (class "Default")
      (node (ref "U1") (pin "42") (pinfunction "RADIO_A_MISO_42") (pintype "passive"))
      (node (ref "U3") (pin "16") (pinfunction "MISO_TX_16") (pintype "bidirectional"))
    )
    (net (code "103") (name "RADIO_A_MOSI") (class "Default")
      (node (ref "U1") (pin "67") (pinfunction "RADIO_A_MOSI_67") (pintype "passive"))
      (node (ref "U3") (pin "17") (pinfunction "MOSI_RX_17") (pintype "bidirectional"))
    )
    (net (code "104") (name "RADIO_A_NRESET") (class "Default")
      (node (ref "U1") (pin "13") (pinfunction "RADIO_CTRL[3]_13") (pintype "passive"))
      (node (ref "U3") (pin "15") (pinfunction "NRESET_15") (pintype "bidirectional"))
    )
    (net (code "105") (name "RADIO_A_SCK") (class "Default")
      (node (ref "U1") (pin "65") (pinfunction "RADIO_A_SCK_65") (pintype "passive"))
      (node (ref "U3") (pin "18") (pinfunction "SCK_18") (pintype "bidirectional"))
    )
    (net (code "106") (name "RADIO_B_CLK_32M") (class "Default")
      (node (ref "R8") (pin "2") (pinfunction "2_2") (pintype "passive"))
      (node (ref "U2") (pin "14") (pinfunction "BUSY_14") (pintype "bidirectional"))
    )
    (net (code "107") (name "RADIO_B_CLK_O") (class "Default")
      (node (ref "U1") (pin "37") (pinfunction "RADIO_B_IQ[4]_37") (pintype "passive"))
      (node (ref "U2") (pin "11") (pinfunction "DIO5_11") (pintype "bidirectional"))
    )
    (net (code "108") (name "RADIO_B_CSN") (class "Default")
      (node (ref "U1") (pin "18") (pinfunction "RADIO_B_CSN_18") (pintype "passive"))
      (node (ref "U2") (pin "19") (pinfunction "NSS_19") (pintype "bidirectional"))
    )
    (net (code "109") (name "RADIO_B_IQ0") (class "Default")
      (node (ref "U1") (pin "35") (pinfunction "RADIO_B_IQ[0]_35") (pintype "passive"))
      (node (ref "U2") (pin "13") (pinfunction "DIO1_13") (pintype "bidirectional"))
    )
    (net (code "110") (name "RADIO_B_IQ1") (class "Default")
      (node (ref "U1") (pin "36") (pinfunction "RADIO_B_IQ[1]_36") (pintype "passive"))
      (node (ref "U2") (pin "12") (pinfunction "DIO2_12") (pintype "bidirectional"))
    )
    (net (code "111") (name "RADIO_B_IQ2") (class "Default")
      (node (ref "U1") (pin "38") (pinfunction "RADIO_B_IQ[2]_38") (pintype "passive"))
      (node (ref "U2") (pin "5") (pinfunction "DIO3_5") (pintype "bidirectional"))
    )
    (net (code "112") (name "RADIO_B_IQ3") (class "Default")
      (node (ref "U1") (pin "32") (pinfunction "RADIO_B_IQ[3]_32") (pintype "passive"))
      (node (ref "U2") (pin "21") (pinfunction "DIO4_21") (pintype "bidirectional"))
    )
    (net (code "113") (name "RADIO_B_MISO") (class "Default")
      (node (ref "U1") (pin "33") (pinfunction "RADIO_B_MISO_33") (pintype "passive"))
      (node (ref "U2") (pin "16") (pinfunction "MISO_TX_16") (pintype "bidirectional"))
    )
    (net (code "114") (name "RADIO_B_MOSI") (class "Default")
      (node (ref "U1") (pin "19") (pinfunction "RADIO_B_MOSI_19") (pintype "passive"))
      (node (ref "U2") (pin "17") (pinfunction "MOSI_RX_17") (pintype "bidirectional"))
    )
    (net (code "115") (name "RADIO_B_NRESET") (class "Default")
      (node (ref "U1") (pin "28") (pinfunction "RADIO_CTRL[9]_28") (pintype "passive"))
      (node (ref "U2") (pin "15") (pinfunction "NRESET_15") (pintype "bidirectional"))
    )
    (net (code "116") (name "RADIO_B_SCK") (class "Default")
      (node (ref "U1") (pin "21") (pinfunction "RADIO_B_SCK_21") (pintype "passive"))
      (node (ref "U2") (pin "18") (pinfunction "SCK_18") (pintype "bidirectional"))
    )
    (net (code "117") (name "RADIO_CTRL1") (class "Default")
      (node (ref "U1") (pin "11") (pinfunction "RADIO_CTRL[1]_11") (pintype "passive"))
    )
    (net (code "118") (name "RXTX_SW") (class "Default")
      (node (ref "C52") (pin "1") (pinfunction "1_1") (pintype "passive"))
      (node (ref "R34") (pin "2") (pinfunction "2_2") (pintype "passive"))
      (node (ref "U6") (pin "6") (pinfunction "CTX_6") (pintype "input"))
    )
    (net (code "119") (name "RX_ON") (class "Default")
      (node (ref "R21") (pin "1") (pinfunction "1_1") (pintype "passive"))
      (node (ref "U1") (pin "59") (pinfunction "GPIO[4]_59") (pintype "passive"))
    )
    (net (code "120") (name "SWCLK") (class "Default")
      (node (ref "P3") (pin "P$1") (pinfunction "P$1_P$1") (pintype "bidirectional"))
      (node (ref "U9") (pin "24") (pinfunction "PA14_24") (pintype "bidirectional"))
    )
    (net (code "121") (name "SWDIO") (class "Default")
      (node (ref "P4") (pin "P$1") (pinfunction "P$1_P$1") (pintype "bidirectional"))
      (node (ref "U9") (pin "23") (pinfunction "PA13_23") (pintype "bidirectional"))
    )
    (net (code "122") (name "SX1261_BUSY") (class "Default")
      (node (ref "J1") (pin "8") (pinfunction "8_8") (pintype "bidirectional"))
      (node (ref "P17") (pin "P$1") (pinfunction "P$1_P$1") (pintype "bidirectional"))
      (node (ref "U8") (pin "14") (pinfunction "BUSY_14") (pintype "bidirectional"))
      (node (ref "U9") (pin "9") (pinfunction "PA3_9") (pintype "bidirectional"))
    )
    (net (code "123") (name "SX1261_DIO1") (class "Default")
      (node (ref "J1") (pin "33") (pinfunction "33_33") (pintype "bidirectional"))
      (node (ref "P15") (pin "P$1") (pinfunction "P$1_P$1") (pintype "bidirectional"))
      (node (ref "U1") (pin "54") (pinfunction "GPIO[7]_54") (pintype "passive"))
      (node (ref "U8") (pin "13") (pinfunction "DIO1_13") (pintype "bidirectional"))
      (node (ref "U9") (pin "15") (pinfunction "PB1_15") (pintype "bidirectional"))
    )
    (net (code "124") (name "SX1261_DIO2") (class "Default")
      (node (ref "J1") (pin "31") (pinfunction "31_31") (pintype "bidirectional"))
      (node (ref "P14") (pin "P$1") (pinfunction "P$1_P$1") (pintype "bidirectional"))
      (node (ref "U8") (pin "12") (pinfunction "DIO2_12") (pintype "bidirectional"))
    )
    (net (code "125") (name "SX1261_NRESET") (class "Default")
      (node (ref "J1") (pin "10") (pinfunction "10_10") (pintype "bidirectional"))
      (node (ref "P18") (pin "P$1") (pinfunction "P$1_P$1") (pintype "bidirectional"))
      (node (ref "R40") (pin "1") (pinfunction "1_1") (pintype "passive"))
      (node (ref "U8") (pin "15") (pinfunction "NRESET_15") (pintype "bidirectional"))
      (node (ref "U9") (pin "18") (pinfunction "PA8_18") (pintype "bidirectional"))
    )
    (net (code "126") (name "SX1261_NSS") (class "Default")
      (node (ref "J1") (pin "25") (pinfunction "25_25") (pintype "bidirectional"))
      (node (ref "P13") (pin "P$1") (pinfunction "P$1_P$1") (pintype "bidirectional"))
      (node (ref "R39") (pin "1") (pinfunction "1_1") (pintype "passive"))
      (node (ref "R41") (pin "1") (pinfunction "1_1") (pintype "passive"))
      (node (ref "U9") (pin "14") (pinfunction "PB0_14") (pintype "bidirectional"))
    )
    (net (code "127") (name "SX1302_CSD") (class "Default")
      (node (ref "R33") (pin "1") (pinfunction "1_1") (pintype "passive"))
      (node (ref "R4") (pin "1") (pinfunction "1_1") (pintype "passive"))
      (node (ref "U1") (pin "10") (pinfunction "RADIO_CTRL[0]_10") (pintype "passive"))
    )
    (net (code "128") (name "SX1302_GPIO8") (class "Default")
      (node (ref "U1") (pin "53") (pinfunction "GPIO[8]_53") (pintype "passive"))
      (node (ref "U9") (pin "26") (pinfunction "PB3_26") (pintype "bidirectional"))
    )
    (net (code "129") (name "SX1302_PA_ON") (class "Default")
      (node (ref "R35") (pin "1") (pinfunction "1_1") (pintype "passive"))
      (node (ref "U1") (pin "16") (pinfunction "RADIO_CTRL[4]_16") (pintype "passive"))
    )
    (net (code "130") (name "SX1302_RESET") (class "Default")
      (node (ref "C63") (pin "2") (pinfunction "2_2") (pintype "passive"))
      (node (ref "D4") (pin "-") (pinfunction "-_-") (pintype "passive"))
      (node (ref "R5") (pin "2") (pinfunction "2_2") (pintype "passive"))
      (node (ref "U1") (pin "7") (pinfunction "RESET_7") (pintype "passive"))
      (node (ref "U9") (pin "8") (pinfunction "PA2_8") (pintype "bidirectional"))
    )
    (net (code "131") (name "SX1302_RXTX_SW") (class "Default")
      (node (ref "R34") (pin "1") (pinfunction "1_1") (pintype "passive"))
      (node (ref "U1") (pin "12") (pinfunction "RADIO_CTRL[2]_12") (pintype "passive"))
    )
    (net (code "132") (name "TCXO_32M_O") (class "Default")
      (node (ref "R24") (pin "2") (pinfunction "2_2") (pintype "passive"))
      (node (ref "R26") (pin "2") (pinfunction "2_2") (pintype "passive"))
      (node (ref "R28") (pin "2") (pinfunction "2_2") (pintype "passive"))
      (node (ref "R37") (pin "2") (pinfunction "2_2") (pintype "passive"))
    )
    (net (code "133") (name "TX_ON") (class "Default")
      (node (ref "R23") (pin "1") (pinfunction "1_1") (pintype "passive"))
      (node (ref "U1") (pin "63") (pinfunction "GPIO[2]_63") (pintype "passive"))
    )
    (net (code "134") (name "USB_D+") (class "Default")
      (node (ref "R9") (pin "2") (pinfunction "2_2") (pintype "passive"))
      (node (ref "U9") (pin "22") (pinfunction "PA12_22") (pintype "bidirectional"))
    )
    (net (code "135") (name "USB_D-") (class "Default")
      (node (ref "R7") (pin "2") (pinfunction "2_2") (pintype "passive"))
      (node (ref "U9") (pin "21") (pinfunction "PA11_21") (pintype "bidirectional"))
    )
    (net (code "136") (name "VCCIO33") (class "Default")
      (node (ref "C10") (pin "2") (pinfunction "2_2") (pintype "passive"))
      (node (ref "C12") (pin "2") (pinfunction "2_2") (pintype "passive"))
      (node (ref "C3") (pin "2") (pinfunction "2_2") (pintype "passive"))
      (node (ref "C4") (pin "2") (pinfunction "2_2") (pintype "passive"))
      (node (ref "C7") (pin "2") (pinfunction "2_2") (pintype "passive"))
      (node (ref "C8") (pin "2") (pinfunction "2_2") (pintype "passive"))
      (node (ref "C83") (pin "2") (pinfunction "2_2") (pintype "passive"))
      (node (ref "C84") (pin "2") (pinfunction "2_2") (pintype "passive"))
      (node (ref "Q1") (pin "3") (pinfunction "D_3") (pintype "passive"))
      (node (ref "R1") (pin "2") (pinfunction "2_2") (pintype "passive"))
      (node (ref "R19") (pin "2") (pinfunction "2_2") (pintype "passive"))
      (node (ref "R20") (pin "2") (pinfunction "2_2") (pintype "passive"))
      (node (ref "R4") (pin "2") (pinfunction "2_2") (pintype "passive"))
      (node (ref "R54") (pin "2") (pinfunction "2_2") (pintype "passive"))
      (node (ref "U1") (pin "14") (pinfunction "VCC_IO_14") (pintype "power_in"))
      (node (ref "U1") (pin "30") (pinfunction "VCC_IO_30") (pintype "power_in"))
      (node (ref "U1") (pin "47") (pinfunction "VCC_IO_47") (pintype "power_in"))
      (node (ref "U1") (pin "61") (pinfunction "VCC_IO_61") (pintype "power_in"))
    )
    (net (code "137") (name "VCC_FEM") (class "Default")
      (node (ref "C35") (pin "2") (pinfunction "2_2") (pintype "passive"))
      (node (ref "C36") (pin "2") (pinfunction "2_2") (pintype "passive"))
      (node (ref "C37") (pin "2") (pinfunction "2_2") (pintype "passive"))
      (node (ref "C38") (pin "2") (pinfunction "2_2") (pintype "passive"))
      (node (ref "C39") (pin "2") (pinfunction "2_2") (pintype "passive"))
      (node (ref "C82") (pin "2") (pinfunction "2_2") (pintype "passive"))
      (node (ref "FB6") (pin "2") (pinfunction "2_2") (pintype "passive"))
      (node (ref "L10") (pin "2") (pinfunction "2_2") (pintype "passive"))
      (node (ref "L11") (pin "2") (pinfunction "2_2") (pintype "passive"))
      (node (ref "U6") (pin "15") (pinfunction "VCC0_15") (pintype "power_in"))
    )
    (net (code "138") (name "VCORE12") (class "Default")
      (node (ref "C1") (pin "2") (pinfunction "2_2") (pintype "passive"))
      (node (ref "C11") (pin "2") (pinfunction "2_2") (pintype "passive"))
      (node (ref "C2") (pin "2") (pinfunction "2_2") (pintype "passive"))
      (node (ref "C5") (pin "2") (pinfunction "2_2") (pintype "passive"))
      (node (ref "C6") (pin "2") (pinfunction "2_2") (pintype "passive"))
      (node (ref "C79") (pin "2") (pinfunction "2_2") (pintype "passive"))
      (node (ref "C9") (pin "2") (pinfunction "2_2") (pintype "passive"))
      (node (ref "FB3") (pin "2") (pinfunction "2_2") (pintype "passive"))
      (node (ref "P23") (pin "P$1") (pinfunction "P$1_P$1") (pintype "bidirectional"))
      (node (ref "R18") (pin "2") (pinfunction "2_2") (pintype "passive"))
      (node (ref "U1") (pin "23") (pinfunction "VCC_CORE_23") (pintype "power_in"))
      (node (ref "U1") (pin "40") (pinfunction "VCC_CORE_40") (pintype "power_in"))
      (node (ref "U1") (pin "5") (pinfunction "VCC_CORE_5") (pintype "power_in"))
      (node (ref "U1") (pin "56") (pinfunction "VCC_CORE_56") (pintype "power_in"))
    )
    (net (code "139") (name "VDD_RADIO") (class "Default")
      (node (ref "C17") (pin "2") (pinfunction "2_2") (pintype "passive"))
      (node (ref "C23") (pin "2") (pinfunction "2_2") (pintype "passive"))
      (node (ref "C57") (pin "2") (pinfunction "2_2") (pintype "passive"))
      (node (ref "C81") (pin "2") (pinfunction "2_2") (pintype "passive"))
      (node (ref "FB1") (pin "1") (pinfunction "1_1") (pintype "passive"))
      (node (ref "FB5") (pin "2") (pinfunction "2_2") (pintype "passive"))
      (node (ref "R25") (pin "2") (pinfunction "2_2") (pintype "passive"))
      (node (ref "R27") (pin "2") (pinfunction "2_2") (pintype "passive"))
      (node (ref "R36") (pin "2") (pinfunction "2_2") (pintype "passive"))
      (node (ref "R39") (pin "2") (pinfunction "2_2") (pintype "passive"))
      (node (ref "R40") (pin "2") (pinfunction "2_2") (pintype "passive"))
      (node (ref "U2") (pin "10") (pinfunction "VBAT_DIO_10") (pintype "bidirectional"))
      (node (ref "U2") (pin "9") (pinfunction "VBAT_RF_9") (pintype "bidirectional"))
      (node (ref "U3") (pin "10") (pinfunction "VBAT_DIO_10") (pintype "bidirectional"))
      (node (ref "U3") (pin "9") (pinfunction "VBAT_RF_9") (pintype "bidirectional"))
      (node (ref "U8") (pin "10") (pinfunction "VBAT_10") (pintype "bidirectional"))
      (node (ref "U8") (pin "11") (pinfunction "VBAT_IO_11") (pintype "bidirectional"))
    )
    (net (code "140") (name "unconnected-(J1-1V5-Pad6)") (class "Default")
      (node (ref "J1") (pin "6") (pinfunction "1V5_6") (pintype "bidirectional"))
    )
    (net (code "141") (name "unconnected-(J1-1V5-Pad28)") (class "Default")
      (node (ref "J1") (pin "28") (pinfunction "1V5_28") (pintype "bidirectional"))
    )
    (net (code "142") (name "unconnected-(J1-1V5-Pad48)") (class "Default")
      (node (ref "J1") (pin "48") (pinfunction "1V5_48") (pintype "bidirectional"))
    )
    (net (code "143") (name "unconnected-(J1-Pad1)") (class "Default")
      (node (ref "J1") (pin "1") (pinfunction "1_1") (pintype "bidirectional"))
    )
    (net (code "144") (name "unconnected-(J1-Pad3)") (class "Default")
      (node (ref "J1") (pin "3") (pinfunction "3_3") (pintype "bidirectional"))
    )
    (net (code "145") (name "unconnected-(J1-Pad5)") (class "Default")
      (node (ref "J1") (pin "5") (pinfunction "5_5") (pintype "bidirectional"))
    )
    (net (code "146") (name "unconnected-(J1-Pad7)") (class "Default")
      (node (ref "J1") (pin "7") (pinfunction "7_7") (pintype "bidirectional"))
    )
    (net (code "147") (name "unconnected-(J1-Pad11)") (class "Default")
      (node (ref "J1") (pin "11") (pinfunction "11_11") (pintype "bidirectional"))
    )
    (net (code "148") (name "unconnected-(J1-Pad12)") (class "Default")
      (node (ref "J1") (pin "12") (pinfunction "12_12") (pintype "bidirectional"))
    )
    (net (code "149") (name "unconnected-(J1-Pad13)") (class "Default")
      (node (ref "J1") (pin "13") (pinfunction "13_13") (pintype "bidirectional"))
    )
    (net (code "150") (name "unconnected-(J1-Pad14)") (class "Default")
      (node (ref "J1") (pin "14") (pinfunction "14_14") (pintype "bidirectional"))
    )
    (net (code "151") (name "unconnected-(J1-Pad16)") (class "Default")
      (node (ref "J1") (pin "16") (pinfunction "16_16") (pintype "bidirectional"))
    )
    (net (code "152") (name "unconnected-(J1-Pad17)") (class "Default")
      (node (ref "J1") (pin "17") (pinfunction "17_17") (pintype "bidirectional"))
    )
    (net (code "153") (name "unconnected-(J1-Pad20)") (class "Default")
      (node (ref "J1") (pin "20") (pinfunction "20_20") (pintype "bidirectional"))
    )
    (net (code "154") (name "unconnected-(J1-Pad23)") (class "Default")
      (node (ref "J1") (pin "23") (pinfunction "23_23") (pintype "bidirectional"))
    )
    (net (code "155") (name "unconnected-(J1-Pad42)") (class "Default")
      (node (ref "J1") (pin "42") (pinfunction "42_42") (pintype "bidirectional"))
    )
    (net (code "156") (name "unconnected-(J1-Pad44)") (class "Default")
      (node (ref "J1") (pin "44") (pinfunction "44_44") (pintype "bidirectional"))
    )
    (net (code "157") (name "unconnected-(J1-Pad46)") (class "Default")
      (node (ref "J1") (pin "46") (pinfunction "46_46") (pintype "bidirectional"))
    )
    (net (code "158") (name "unconnected-(U1-GPIO[1]-Pad64)") (class "Default")
      (node (ref "U1") (pin "64") (pinfunction "GPIO[1]_64") (pintype "passive"))
    )
    (net (code "159") (name "unconnected-(U1-GPIO[3]-Pad60)") (class "Default")
      (node (ref "U1") (pin "60") (pinfunction "GPIO[3]_60") (pintype "passive"))
    )
    (net (code "160") (name "unconnected-(U1-GPIO[5]-Pad58)") (class "Default")
      (node (ref "U1") (pin "58") (pinfunction "GPIO[5]_58") (pintype "passive"))
    )
    (net (code "161") (name "unconnected-(U1-RADIO_CTRL[5]-Pad17)") (class "Default")
      (node (ref "U1") (pin "17") (pinfunction "RADIO_CTRL[5]_17") (pintype "passive"))
    )
    (net (code "162") (name "unconnected-(U1-RADIO_CTRL[6]-Pad22)") (class "Default")
      (node (ref "U1") (pin "22") (pinfunction "RADIO_CTRL[6]_22") (pintype "passive"))
    )
    (net (code "163") (name "unconnected-(U1-RADIO_CTRL[7]-Pad26)") (class "Default")
      (node (ref "U1") (pin "26") (pinfunction "RADIO_CTRL[7]_26") (pintype "passive"))
    )
    (net (code "164") (name "unconnected-(U1-RADIO_CTRL[8]-Pad27)") (class "Default")
      (node (ref "U1") (pin "27") (pinfunction "RADIO_CTRL[8]_27") (pintype "passive"))
    )
    (net (code "165") (name "unconnected-(U1-RADIO_CTRL[10]-Pad29)") (class "Default")
      (node (ref "U1") (pin "29") (pinfunction "RADIO_CTRL[10]_29") (pintype "passive"))
    )
    (net (code "166") (name "unconnected-(U1-RADIO_CTRL[11]-Pad31)") (class "Default")
      (node (ref "U1") (pin "31") (pinfunction "RADIO_CTRL[11]_31") (pintype "passive"))
    )
    (net (code "167") (name "unconnected-(U2-RFO-Pad24)") (class "Default")
      (node (ref "U2") (pin "24") (pinfunction "RFO_24") (pintype "bidirectional"))
    )
    (net (code "168") (name "unconnected-(U2-VR_PA-Pad1)") (class "Default")
      (node (ref "U2") (pin "1") (pinfunction "VR_PA_1") (pintype "bidirectional"))
    )
    (net (code "169") (name "unconnected-(U2-XTB-Pad4)") (class "Default")
      (node (ref "U2") (pin "4") (pinfunction "XTB_4") (pintype "bidirectional"))
    )
    (net (code "170") (name "unconnected-(U3-XTB-Pad4)") (class "Default")
      (node (ref "U3") (pin "4") (pinfunction "XTB_4") (pintype "bidirectional"))
    )
    (net (code "171") (name "unconnected-(U6-N{slash}C-Pad14)") (class "Default")
      (node (ref "U6") (pin "14") (pinfunction "N/C_14") (pintype "passive"))
    )
    (net (code "172") (name "unconnected-(U6-TX_ALT-Pad3)") (class "Default")
      (node (ref "U6") (pin "3") (pinfunction "TX_ALT_3") (pintype "passive"))
    )
    (net (code "173") (name "unconnected-(U8-RFO-Pad23)") (class "Default")
      (node (ref "U8") (pin "23") (pinfunction "RFO_23") (pintype "bidirectional"))
    )
    (net (code "174") (name "unconnected-(U8-VR_PA-Pad24)") (class "Default")
      (node (ref "U8") (pin "24") (pinfunction "VR_PA_24") (pintype "bidirectional"))
    )
    (net (code "175") (name "unconnected-(U8-XTB-Pad4)") (class "Default")
      (node (ref "U8") (pin "4") (pinfunction "XTB_4") (pintype "bidirectional"))
    )
    (net (code "176") (name "unconnected-(U9-PA9-Pad19)") (class "Default")
      (node (ref "U9") (pin "19") (pinfunction "PA9_19") (pintype "bidirectional"))
    )
    (net (code "177") (name "unconnected-(U9-PA10-Pad20)") (class "Default")
      (node (ref "U9") (pin "20") (pinfunction "PA10_20") (pintype "bidirectional"))
    )
    (net (code "178") (name "unconnected-(U9-PA15-Pad25)") (class "Default")
      (node (ref "U9") (pin "25") (pinfunction "PA15_25") (pintype "bidirectional"))
    )
    (net (code "179") (name "unconnected-(U9-PB5-Pad28)") (class "Default")
      (node (ref "U9") (pin "28") (pinfunction "PB5_28") (pintype "bidirectional"))
    )
  )
)
